# PwrAndBias.net
KiCad netlist of a schematic drawn in Altium Designer
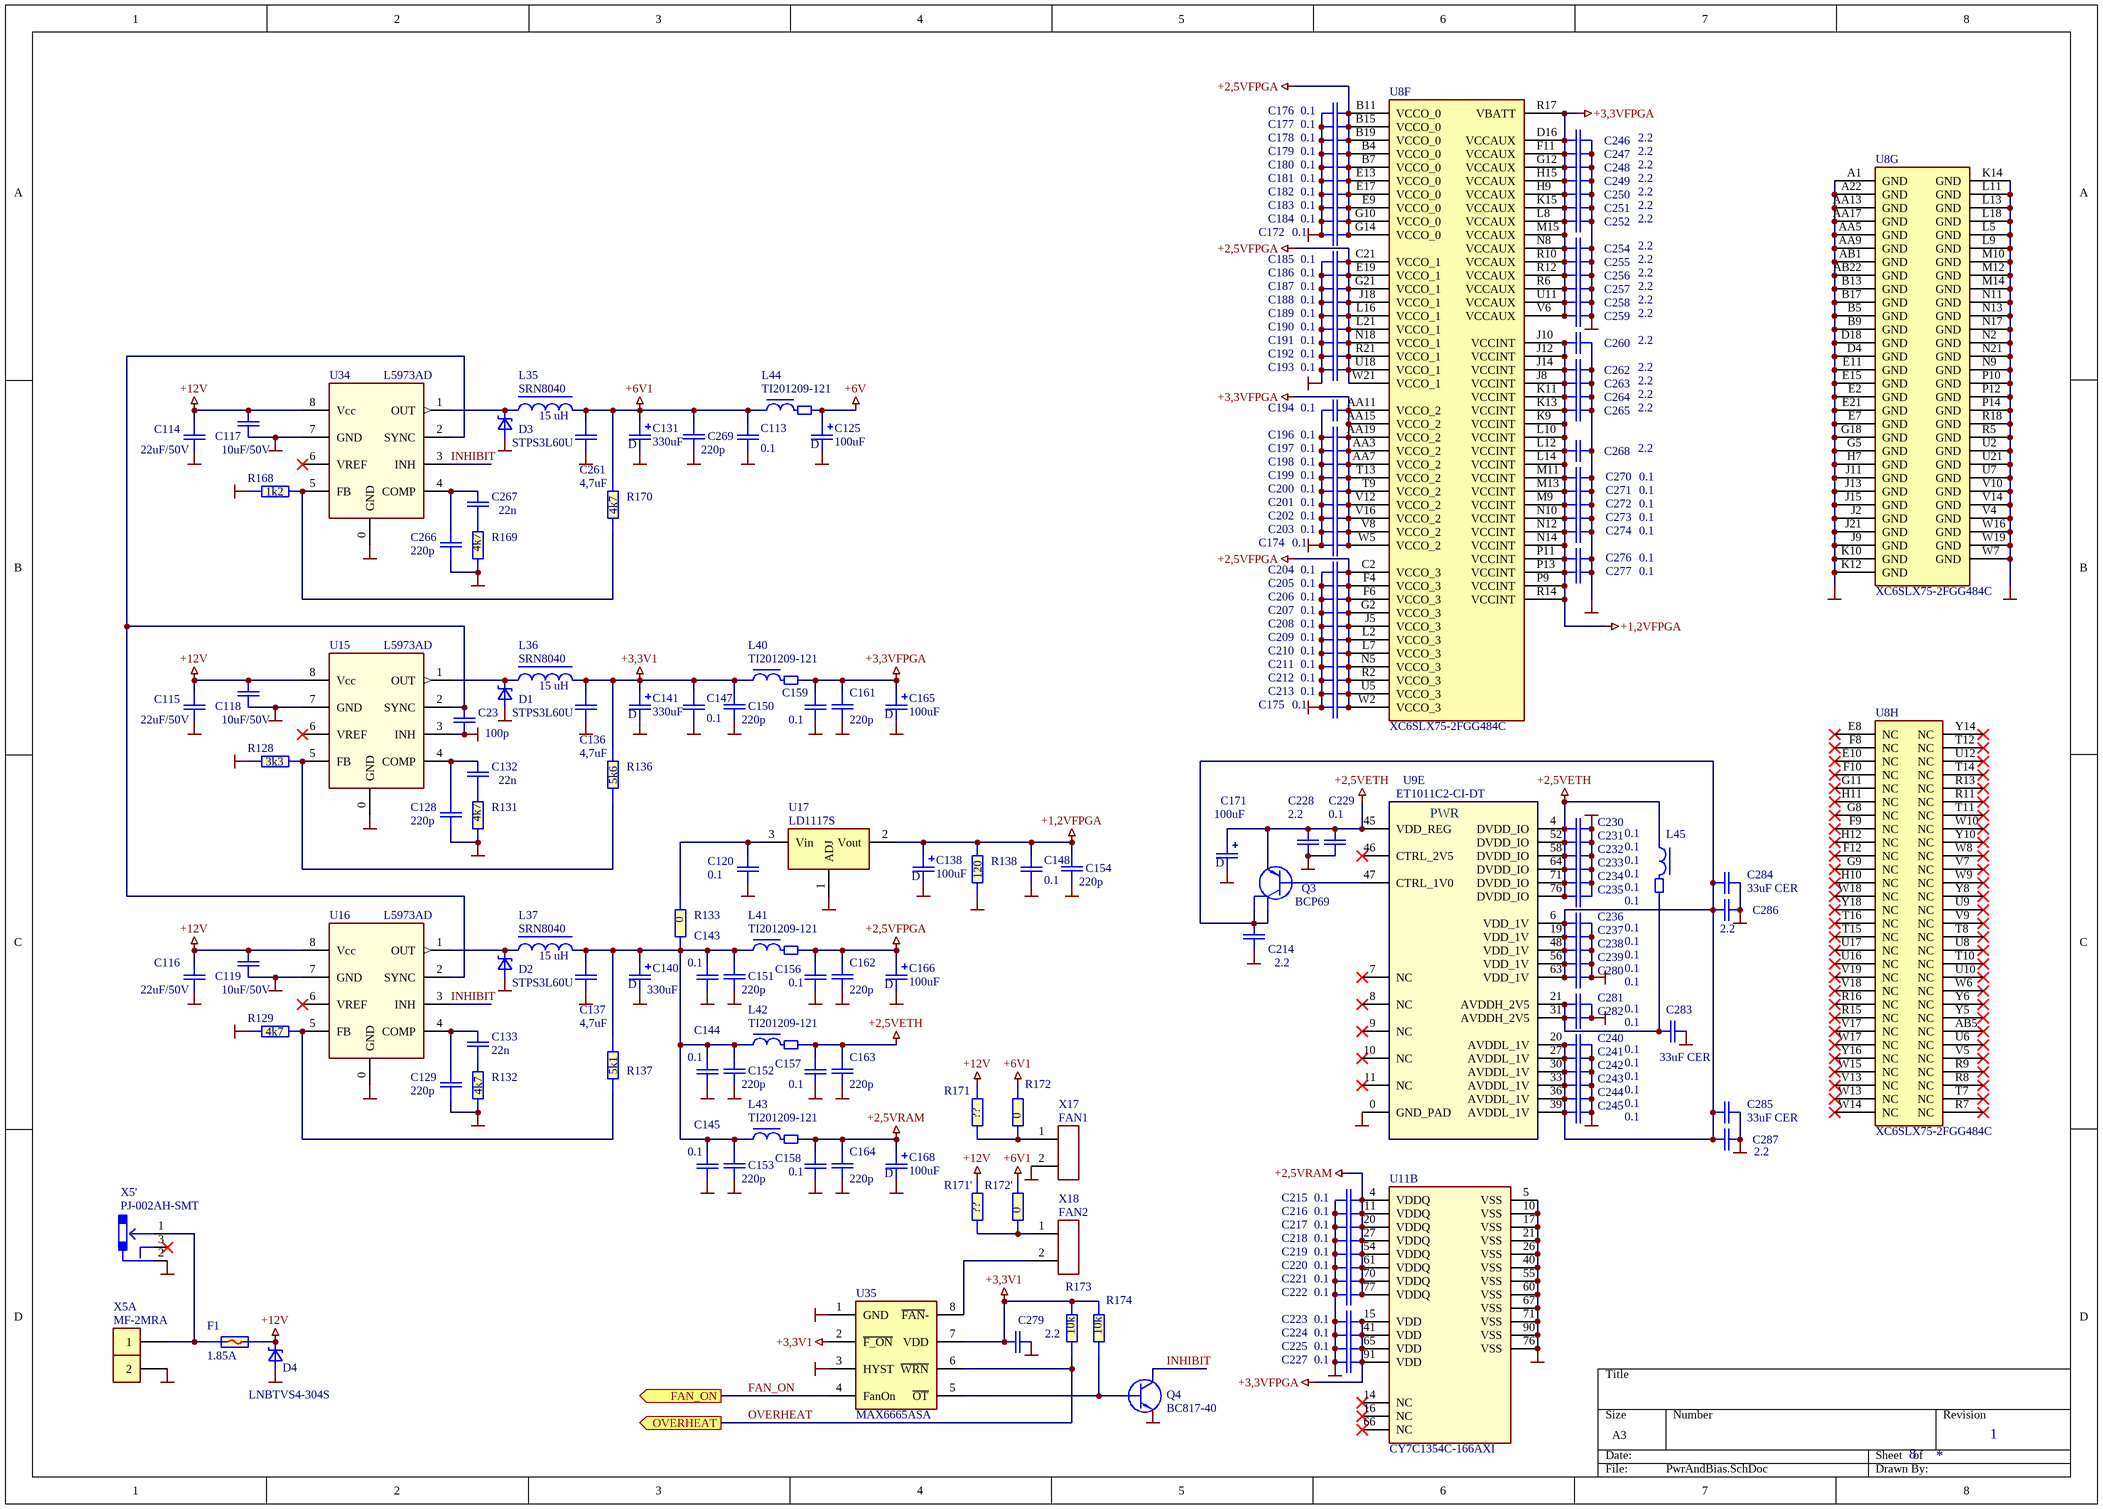
[diagram p0: PwrAndBias.SchDoc]

(export (version "E")
  (design (tool "Eeschema 10.0.6"))
  (components
    (comp (ref "C23")
      (value "100p")
      (footprint "C0603-PHILLIPS")
      (description "Конденсатор")
      (fields (field (name "MANUFACTURER") "MURATA") (field (name "TOLERANCE") "20%"))
      (libsource (lib "altium-import") (part "root_0_mirrored_C0603_"))
    )
    (comp (ref "C113")
      (value "0.1")
      (footprint "C0402-Phillips")
      (description "Конденсатор")
      (fields (field (name "MANUFACTURER") "MURATA") (field (name "TOLERANCE") "20%"))
      (libsource (lib "Capacitors") (part "C0402"))
    )
    (comp (ref "C114")
      (value "22uF/50V")
      (footprint "C2220")
      (description "Конденсатор")
      (fields (field (name "MANUFACTURER") "TDK"))
      (libsource (lib "Capacitors") (part "C2220"))
    )
    (comp (ref "C115")
      (value "22uF/50V")
      (footprint "C2220")
      (description "Конденсатор")
      (fields (field (name "MANUFACTURER") "TDK"))
      (libsource (lib "Capacitors") (part "C2220"))
    )
    (comp (ref "C116")
      (value "22uF/50V")
      (footprint "C2220")
      (description "Конденсатор")
      (fields (field (name "MANUFACTURER") "TDK"))
      (libsource (lib "Capacitors") (part "C2220"))
    )
    (comp (ref "C117")
      (value "10uF/50V")
      (footprint "C1210_H2,5")
      (description "Конденсатор")
      (fields (field (name "MANUFACTURER") "TAIYO YUDEN") (field (name "TOLERANCE") "20%"))
      (libsource (lib "Andy") (part "C1210_H2,5"))
    )
    (comp (ref "C118")
      (value "10uF/50V")
      (footprint "C1210_H2,5")
      (description "Конденсатор")
      (fields (field (name "MANUFACTURER") "TAIYO YUDEN") (field (name "TOLERANCE") "20%"))
      (libsource (lib "Andy") (part "C1210_H2,5"))
    )
    (comp (ref "C119")
      (value "10uF/50V")
      (footprint "C1210_H2,5")
      (description "Конденсатор")
      (fields (field (name "MANUFACTURER") "TAIYO YUDEN") (field (name "TOLERANCE") "20%"))
      (libsource (lib "Andy") (part "C1210_H2,5"))
    )
    (comp (ref "C120")
      (value "0.1")
      (footprint "C0402-Phillips")
      (description "Конденсатор")
      (fields (field (name "MANUFACTURER") "MURATA") (field (name "TOLERANCE") "20%"))
      (libsource (lib "Capacitors") (part "C0402"))
    )
    (comp (ref "C125")
      (value "100uF")
      (footprint "cd7343")
      (description "Конденсатор")
      (fields (field (name "MANUFACTURER") "SPRAGUE"))
      (libsource (lib "altium-import") (part "root_0_CD7343_"))
    )
    (comp (ref "C128")
      (value "220p")
      (footprint "C0603-PHILLIPS")
      (description "Конденсатор")
      (fields (field (name "MANUFACTURER") "MURATA") (field (name "TOLERANCE") "20%"))
      (libsource (lib "altium-import") (part "root_0_C0603_"))
    )
    (comp (ref "C129")
      (value "220p")
      (footprint "C0603-PHILLIPS")
      (description "Конденсатор")
      (fields (field (name "MANUFACTURER") "MURATA") (field (name "TOLERANCE") "20%"))
      (libsource (lib "altium-import") (part "root_0_C0603_"))
    )
    (comp (ref "C131")
      (value "330uF")
      (footprint "cd7343")
      (description "Конденсатор")
      (fields (field (name "MANUFACTURER") "Kemet"))
      (libsource (lib "altium-import") (part "root_0_CD7343_"))
    )
    (comp (ref "C132")
      (value "22n")
      (footprint "C0603-PHILLIPS")
      (description "Конденсатор")
      (fields (field (name "MANUFACTURER") "MURATA") (field (name "TOLERANCE") "20%"))
      (libsource (lib "altium-import") (part "root_0_C0603_"))
    )
    (comp (ref "C133")
      (value "22n")
      (footprint "C0603-PHILLIPS")
      (description "Конденсатор")
      (fields (field (name "MANUFACTURER") "MURATA") (field (name "TOLERANCE") "20%"))
      (libsource (lib "altium-import") (part "root_0_C0603_"))
    )
    (comp (ref "C136")
      (value "4,7uF")
      (footprint "c1206")
      (description "Конденсатор")
      (fields (field (name "MANUFACTURER") "Taiyo Yuden") (field (name "TOLERANCE") "10%"))
      (libsource (lib "altium-import") (part "root_0_C1206_"))
    )
    (comp (ref "C137")
      (value "4,7uF")
      (footprint "c1206")
      (description "Конденсатор")
      (fields (field (name "MANUFACTURER") "Taiyo Yuden") (field (name "TOLERANCE") "10%"))
      (libsource (lib "altium-import") (part "root_0_C1206_"))
    )
    (comp (ref "C138")
      (value "100uF")
      (footprint "cd7343")
      (description "Конденсатор")
      (fields (field (name "MANUFACTURER") "SPRAGUE"))
      (libsource (lib "altium-import") (part "root_0_CD7343_"))
    )
    (comp (ref "C140")
      (value "330uF")
      (footprint "cd7343")
      (description "Конденсатор")
      (fields (field (name "MANUFACTURER") "Kemet"))
      (libsource (lib "altium-import") (part "root_0_CD7343_"))
    )
    (comp (ref "C141")
      (value "330uF")
      (footprint "cd7343")
      (description "Конденсатор")
      (fields (field (name "MANUFACTURER") "Kemet"))
      (libsource (lib "altium-import") (part "root_0_CD7343_"))
    )
    (comp (ref "C143")
      (value "0.1")
      (footprint "C0402-Phillips")
      (description "Конденсатор")
      (fields (field (name "MANUFACTURER") "MURATA") (field (name "TOLERANCE") "20%"))
      (libsource (lib "Capacitors") (part "C0402"))
    )
    (comp (ref "C144")
      (value "0.1")
      (footprint "C0402-Phillips")
      (description "Конденсатор")
      (fields (field (name "MANUFACTURER") "MURATA") (field (name "TOLERANCE") "20%"))
      (libsource (lib "Capacitors") (part "C0402"))
    )
    (comp (ref "C145")
      (value "0.1")
      (footprint "C0402-Phillips")
      (description "Конденсатор")
      (fields (field (name "MANUFACTURER") "MURATA") (field (name "TOLERANCE") "20%"))
      (libsource (lib "Capacitors") (part "C0402"))
    )
    (comp (ref "C147")
      (value "0.1")
      (footprint "C0402-Phillips")
      (description "Конденсатор")
      (fields (field (name "MANUFACTURER") "MURATA") (field (name "TOLERANCE") "20%"))
      (libsource (lib "Capacitors") (part "C0402"))
    )
    (comp (ref "C148")
      (value "0.1")
      (footprint "C0402-Phillips")
      (description "Конденсатор")
      (fields (field (name "MANUFACTURER") "MURATA") (field (name "TOLERANCE") "20%"))
      (libsource (lib "Capacitors") (part "C0402"))
    )
    (comp (ref "C150")
      (value "220p")
      (footprint "C0603-PHILLIPS")
      (description "Конденсатор")
      (fields (field (name "MANUFACTURER") "MURATA") (field (name "TOLERANCE") "20%"))
      (libsource (lib "altium-import") (part "root_0_C0603_"))
    )
    (comp (ref "C151")
      (value "220p")
      (footprint "C0603-PHILLIPS")
      (description "Конденсатор")
      (fields (field (name "MANUFACTURER") "MURATA") (field (name "TOLERANCE") "20%"))
      (libsource (lib "altium-import") (part "root_0_C0603_"))
    )
    (comp (ref "C152")
      (value "220p")
      (footprint "C0603-PHILLIPS")
      (description "Конденсатор")
      (fields (field (name "MANUFACTURER") "MURATA") (field (name "TOLERANCE") "20%"))
      (libsource (lib "altium-import") (part "root_0_C0603_"))
    )
    (comp (ref "C153")
      (value "220p")
      (footprint "C0603-PHILLIPS")
      (description "Конденсатор")
      (fields (field (name "MANUFACTURER") "MURATA") (field (name "TOLERANCE") "20%"))
      (libsource (lib "altium-import") (part "root_0_C0603_"))
    )
    (comp (ref "C154")
      (value "220p")
      (footprint "C0603-PHILLIPS")
      (description "Конденсатор")
      (fields (field (name "MANUFACTURER") "MURATA") (field (name "TOLERANCE") "20%"))
      (libsource (lib "altium-import") (part "root_0_C0603_"))
    )
    (comp (ref "C156")
      (value "0.1")
      (footprint "C0402-Phillips")
      (description "Конденсатор")
      (fields (field (name "MANUFACTURER") "MURATA") (field (name "TOLERANCE") "20%"))
      (libsource (lib "Capacitors") (part "C0402"))
    )
    (comp (ref "C157")
      (value "0.1")
      (footprint "C0402-Phillips")
      (description "Конденсатор")
      (fields (field (name "MANUFACTURER") "MURATA") (field (name "TOLERANCE") "20%"))
      (libsource (lib "Capacitors") (part "C0402"))
    )
    (comp (ref "C158")
      (value "0.1")
      (footprint "C0402-Phillips")
      (description "Конденсатор")
      (fields (field (name "MANUFACTURER") "MURATA") (field (name "TOLERANCE") "20%"))
      (libsource (lib "Capacitors") (part "C0402"))
    )
    (comp (ref "C159")
      (value "0.1")
      (footprint "C0402-Phillips")
      (description "Конденсатор")
      (fields (field (name "MANUFACTURER") "MURATA") (field (name "TOLERANCE") "20%"))
      (libsource (lib "Capacitors") (part "C0402"))
    )
    (comp (ref "C161")
      (value "220p")
      (footprint "C0603-PHILLIPS")
      (description "Конденсатор")
      (fields (field (name "MANUFACTURER") "MURATA") (field (name "TOLERANCE") "20%"))
      (libsource (lib "altium-import") (part "root_0_C0603_"))
    )
    (comp (ref "C162")
      (value "220p")
      (footprint "C0603-PHILLIPS")
      (description "Конденсатор")
      (fields (field (name "MANUFACTURER") "MURATA") (field (name "TOLERANCE") "20%"))
      (libsource (lib "altium-import") (part "root_0_C0603_"))
    )
    (comp (ref "C163")
      (value "220p")
      (footprint "C0603-PHILLIPS")
      (description "Конденсатор")
      (fields (field (name "MANUFACTURER") "MURATA") (field (name "TOLERANCE") "20%"))
      (libsource (lib "altium-import") (part "root_0_C0603_"))
    )
    (comp (ref "C164")
      (value "220p")
      (footprint "C0603-PHILLIPS")
      (description "Конденсатор")
      (fields (field (name "MANUFACTURER") "MURATA") (field (name "TOLERANCE") "20%"))
      (libsource (lib "altium-import") (part "root_0_C0603_"))
    )
    (comp (ref "C165")
      (value "100uF")
      (footprint "cd7343")
      (description "Конденсатор")
      (fields (field (name "MANUFACTURER") "SPRAGUE"))
      (libsource (lib "altium-import") (part "root_0_CD7343_"))
    )
    (comp (ref "C166")
      (value "100uF")
      (footprint "cd7343")
      (description "Конденсатор")
      (fields (field (name "MANUFACTURER") "SPRAGUE"))
      (libsource (lib "altium-import") (part "root_0_CD7343_"))
    )
    (comp (ref "C168")
      (value "100uF")
      (footprint "cd7343")
      (description "Конденсатор")
      (fields (field (name "MANUFACTURER") "SPRAGUE"))
      (libsource (lib "altium-import") (part "root_0_CD7343_"))
    )
    (comp (ref "C171")
      (value "100uF")
      (footprint "cd7343")
      (description "Конденсатор")
      (fields (field (name "MANUFACTURER") "SPRAGUE"))
      (libsource (lib "altium-import") (part "root_0_CD7343_"))
    )
    (comp (ref "C172")
      (value "0.1")
      (footprint "C0402-cirq")
      (description "Конденсатор")
      (fields (field (name "MANUFACTURER") "MURATA") (field (name "TOLERANCE") "20%"))
      (libsource (lib "Capacitors") (part "C0402"))
    )
    (comp (ref "C174")
      (value "0.1")
      (footprint "C0402-cirq")
      (description "Конденсатор")
      (fields (field (name "MANUFACTURER") "MURATA") (field (name "TOLERANCE") "20%"))
      (libsource (lib "Capacitors") (part "C0402"))
    )
    (comp (ref "C175")
      (value "0.1")
      (footprint "C0402-cirq")
      (description "Конденсатор")
      (fields (field (name "MANUFACTURER") "MURATA") (field (name "TOLERANCE") "20%"))
      (libsource (lib "Capacitors") (part "C0402"))
    )
    (comp (ref "C176")
      (value "0.1")
      (footprint "C0402-cirq")
      (description "Конденсатор")
      (fields (field (name "MANUFACTURER") "MURATA") (field (name "TOLERANCE") "20%"))
      (libsource (lib "Capacitors") (part "C0402"))
    )
    (comp (ref "C177")
      (value "0.1")
      (footprint "C0402-cirq")
      (description "Конденсатор")
      (fields (field (name "MANUFACTURER") "MURATA") (field (name "TOLERANCE") "20%"))
      (libsource (lib "Capacitors") (part "C0402"))
    )
    (comp (ref "C178")
      (value "0.1")
      (footprint "C0402-cirq")
      (description "Конденсатор")
      (fields (field (name "MANUFACTURER") "MURATA") (field (name "TOLERANCE") "20%"))
      (libsource (lib "Capacitors") (part "C0402"))
    )
    (comp (ref "C179")
      (value "0.1")
      (footprint "C0402-cirq")
      (description "Конденсатор")
      (fields (field (name "MANUFACTURER") "MURATA") (field (name "TOLERANCE") "20%"))
      (libsource (lib "Capacitors") (part "C0402"))
    )
    (comp (ref "C180")
      (value "0.1")
      (footprint "C0402-cirq")
      (description "Конденсатор")
      (fields (field (name "MANUFACTURER") "MURATA") (field (name "TOLERANCE") "20%"))
      (libsource (lib "Capacitors") (part "C0402"))
    )
    (comp (ref "C181")
      (value "0.1")
      (footprint "C0402-cirq")
      (description "Конденсатор")
      (fields (field (name "MANUFACTURER") "MURATA") (field (name "TOLERANCE") "20%"))
      (libsource (lib "Capacitors") (part "C0402"))
    )
    (comp (ref "C182")
      (value "0.1")
      (footprint "C0402-cirq")
      (description "Конденсатор")
      (fields (field (name "MANUFACTURER") "MURATA") (field (name "TOLERANCE") "20%"))
      (libsource (lib "Capacitors") (part "C0402"))
    )
    (comp (ref "C183")
      (value "0.1")
      (footprint "C0402-cirq")
      (description "Конденсатор")
      (fields (field (name "MANUFACTURER") "MURATA") (field (name "TOLERANCE") "20%"))
      (libsource (lib "Capacitors") (part "C0402"))
    )
    (comp (ref "C184")
      (value "0.1")
      (footprint "C0402-cirq")
      (description "Конденсатор")
      (fields (field (name "MANUFACTURER") "MURATA") (field (name "TOLERANCE") "20%"))
      (libsource (lib "Capacitors") (part "C0402"))
    )
    (comp (ref "C185")
      (value "0.1")
      (footprint "C0402-cirq")
      (description "Конденсатор")
      (fields (field (name "MANUFACTURER") "MURATA") (field (name "TOLERANCE") "20%"))
      (libsource (lib "Capacitors") (part "C0402"))
    )
    (comp (ref "C186")
      (value "0.1")
      (footprint "C0402-cirq")
      (description "Конденсатор")
      (fields (field (name "MANUFACTURER") "MURATA") (field (name "TOLERANCE") "20%"))
      (libsource (lib "Capacitors") (part "C0402"))
    )
    (comp (ref "C187")
      (value "0.1")
      (footprint "C0402-cirq")
      (description "Конденсатор")
      (fields (field (name "MANUFACTURER") "MURATA") (field (name "TOLERANCE") "20%"))
      (libsource (lib "Capacitors") (part "C0402"))
    )
    (comp (ref "C188")
      (value "0.1")
      (footprint "C0402-cirq")
      (description "Конденсатор")
      (fields (field (name "MANUFACTURER") "MURATA") (field (name "TOLERANCE") "20%"))
      (libsource (lib "Capacitors") (part "C0402"))
    )
    (comp (ref "C189")
      (value "0.1")
      (footprint "C0402-cirq")
      (description "Конденсатор")
      (fields (field (name "MANUFACTURER") "MURATA") (field (name "TOLERANCE") "20%"))
      (libsource (lib "Capacitors") (part "C0402"))
    )
    (comp (ref "C190")
      (value "0.1")
      (footprint "C0402-cirq")
      (description "Конденсатор")
      (fields (field (name "MANUFACTURER") "MURATA") (field (name "TOLERANCE") "20%"))
      (libsource (lib "Capacitors") (part "C0402"))
    )
    (comp (ref "C191")
      (value "0.1")
      (footprint "C0402-cirq")
      (description "Конденсатор")
      (fields (field (name "MANUFACTURER") "MURATA") (field (name "TOLERANCE") "20%"))
      (libsource (lib "Capacitors") (part "C0402"))
    )
    (comp (ref "C192")
      (value "0.1")
      (footprint "C0402-cirq")
      (description "Конденсатор")
      (fields (field (name "MANUFACTURER") "MURATA") (field (name "TOLERANCE") "20%"))
      (libsource (lib "Capacitors") (part "C0402"))
    )
    (comp (ref "C193")
      (value "0.1")
      (footprint "C0402-cirq")
      (description "Конденсатор")
      (fields (field (name "MANUFACTURER") "MURATA") (field (name "TOLERANCE") "20%"))
      (libsource (lib "Capacitors") (part "C0402"))
    )
    (comp (ref "C194")
      (value "0.1")
      (footprint "C0402-cirq")
      (description "Конденсатор")
      (fields (field (name "MANUFACTURER") "MURATA") (field (name "TOLERANCE") "20%"))
      (libsource (lib "Capacitors") (part "C0402"))
    )
    (comp (ref "C196")
      (value "0.1")
      (footprint "C0402-cirq")
      (description "Конденсатор")
      (fields (field (name "MANUFACTURER") "MURATA") (field (name "TOLERANCE") "20%"))
      (libsource (lib "Capacitors") (part "C0402"))
    )
    (comp (ref "C197")
      (value "0.1")
      (footprint "C0402-cirq")
      (description "Конденсатор")
      (fields (field (name "MANUFACTURER") "MURATA") (field (name "TOLERANCE") "20%"))
      (libsource (lib "Capacitors") (part "C0402"))
    )
    (comp (ref "C198")
      (value "0.1")
      (footprint "C0402-cirq")
      (description "Конденсатор")
      (fields (field (name "MANUFACTURER") "MURATA") (field (name "TOLERANCE") "20%"))
      (libsource (lib "Capacitors") (part "C0402"))
    )
    (comp (ref "C199")
      (value "0.1")
      (footprint "C0402-cirq")
      (description "Конденсатор")
      (fields (field (name "MANUFACTURER") "MURATA") (field (name "TOLERANCE") "20%"))
      (libsource (lib "Capacitors") (part "C0402"))
    )
    (comp (ref "C200")
      (value "0.1")
      (footprint "C0402-cirq")
      (description "Конденсатор")
      (fields (field (name "MANUFACTURER") "MURATA") (field (name "TOLERANCE") "20%"))
      (libsource (lib "Capacitors") (part "C0402"))
    )
    (comp (ref "C201")
      (value "0.1")
      (footprint "C0402-cirq")
      (description "Конденсатор")
      (fields (field (name "MANUFACTURER") "MURATA") (field (name "TOLERANCE") "20%"))
      (libsource (lib "Capacitors") (part "C0402"))
    )
    (comp (ref "C202")
      (value "0.1")
      (footprint "C0402-cirq")
      (description "Конденсатор")
      (fields (field (name "MANUFACTURER") "MURATA") (field (name "TOLERANCE") "20%"))
      (libsource (lib "Capacitors") (part "C0402"))
    )
    (comp (ref "C203")
      (value "0.1")
      (footprint "C0402-cirq")
      (description "Конденсатор")
      (fields (field (name "MANUFACTURER") "MURATA") (field (name "TOLERANCE") "20%"))
      (libsource (lib "Capacitors") (part "C0402"))
    )
    (comp (ref "C204")
      (value "0.1")
      (footprint "C0402-cirq")
      (description "Конденсатор")
      (fields (field (name "MANUFACTURER") "MURATA") (field (name "TOLERANCE") "20%"))
      (libsource (lib "Capacitors") (part "C0402"))
    )
    (comp (ref "C205")
      (value "0.1")
      (footprint "C0402-cirq")
      (description "Конденсатор")
      (fields (field (name "MANUFACTURER") "MURATA") (field (name "TOLERANCE") "20%"))
      (libsource (lib "Capacitors") (part "C0402"))
    )
    (comp (ref "C206")
      (value "0.1")
      (footprint "C0402-cirq")
      (description "Конденсатор")
      (fields (field (name "MANUFACTURER") "MURATA") (field (name "TOLERANCE") "20%"))
      (libsource (lib "Capacitors") (part "C0402"))
    )
    (comp (ref "C207")
      (value "0.1")
      (footprint "C0402-cirq")
      (description "Конденсатор")
      (fields (field (name "MANUFACTURER") "MURATA") (field (name "TOLERANCE") "20%"))
      (libsource (lib "Capacitors") (part "C0402"))
    )
    (comp (ref "C208")
      (value "0.1")
      (footprint "C0402-cirq")
      (description "Конденсатор")
      (fields (field (name "MANUFACTURER") "MURATA") (field (name "TOLERANCE") "20%"))
      (libsource (lib "Capacitors") (part "C0402"))
    )
    (comp (ref "C209")
      (value "0.1")
      (footprint "C0402-cirq")
      (description "Конденсатор")
      (fields (field (name "MANUFACTURER") "MURATA") (field (name "TOLERANCE") "20%"))
      (libsource (lib "Capacitors") (part "C0402"))
    )
    (comp (ref "C210")
      (value "0.1")
      (footprint "C0402-cirq")
      (description "Конденсатор")
      (fields (field (name "MANUFACTURER") "MURATA") (field (name "TOLERANCE") "20%"))
      (libsource (lib "Capacitors") (part "C0402"))
    )
    (comp (ref "C211")
      (value "0.1")
      (footprint "C0402-cirq")
      (description "Конденсатор")
      (fields (field (name "MANUFACTURER") "MURATA") (field (name "TOLERANCE") "20%"))
      (libsource (lib "Capacitors") (part "C0402"))
    )
    (comp (ref "C212")
      (value "0.1")
      (footprint "C0402-cirq")
      (description "Конденсатор")
      (fields (field (name "MANUFACTURER") "MURATA") (field (name "TOLERANCE") "20%"))
      (libsource (lib "Capacitors") (part "C0402"))
    )
    (comp (ref "C213")
      (value "0.1")
      (footprint "C0402-cirq")
      (description "Конденсатор")
      (fields (field (name "MANUFACTURER") "MURATA") (field (name "TOLERANCE") "20%"))
      (libsource (lib "Capacitors") (part "C0402"))
    )
    (comp (ref "C214")
      (value "2.2")
      (footprint "C0402-Phillips")
      (description "Конденсатор")
      (fields (field (name "MANUFACTURER") "MURATA") (field (name "TOLERANCE") "20%"))
      (libsource (lib "Capacitors") (part "C0402"))
    )
    (comp (ref "C215")
      (value "0.1")
      (footprint "C0402-Phillips")
      (description "Конденсатор")
      (fields (field (name "MANUFACTURER") "MURATA") (field (name "TOLERANCE") "20%"))
      (libsource (lib "Capacitors") (part "C0402"))
    )
    (comp (ref "C216")
      (value "0.1")
      (footprint "C0402-Phillips")
      (description "Конденсатор")
      (fields (field (name "MANUFACTURER") "MURATA") (field (name "TOLERANCE") "20%"))
      (libsource (lib "Capacitors") (part "C0402"))
    )
    (comp (ref "C217")
      (value "0.1")
      (footprint "C0402-Phillips")
      (description "Конденсатор")
      (fields (field (name "MANUFACTURER") "MURATA") (field (name "TOLERANCE") "20%"))
      (libsource (lib "Capacitors") (part "C0402"))
    )
    (comp (ref "C218")
      (value "0.1")
      (footprint "C0402-Phillips")
      (description "Конденсатор")
      (fields (field (name "MANUFACTURER") "MURATA") (field (name "TOLERANCE") "20%"))
      (libsource (lib "Capacitors") (part "C0402"))
    )
    (comp (ref "C219")
      (value "0.1")
      (footprint "C0402-Phillips")
      (description "Конденсатор")
      (fields (field (name "MANUFACTURER") "MURATA") (field (name "TOLERANCE") "20%"))
      (libsource (lib "Capacitors") (part "C0402"))
    )
    (comp (ref "C220")
      (value "0.1")
      (footprint "C0402-Phillips")
      (description "Конденсатор")
      (fields (field (name "MANUFACTURER") "MURATA") (field (name "TOLERANCE") "20%"))
      (libsource (lib "Capacitors") (part "C0402"))
    )
    (comp (ref "C221")
      (value "0.1")
      (footprint "C0402-Phillips")
      (description "Конденсатор")
      (fields (field (name "MANUFACTURER") "MURATA") (field (name "TOLERANCE") "20%"))
      (libsource (lib "Capacitors") (part "C0402"))
    )
    (comp (ref "C222")
      (value "0.1")
      (footprint "C0402-Phillips")
      (description "Конденсатор")
      (fields (field (name "MANUFACTURER") "MURATA") (field (name "TOLERANCE") "20%"))
      (libsource (lib "Capacitors") (part "C0402"))
    )
    (comp (ref "C223")
      (value "0.1")
      (footprint "C0402-Phillips")
      (description "Конденсатор")
      (fields (field (name "MANUFACTURER") "MURATA") (field (name "TOLERANCE") "20%"))
      (libsource (lib "Capacitors") (part "C0402"))
    )
    (comp (ref "C224")
      (value "0.1")
      (footprint "C0402-Phillips")
      (description "Конденсатор")
      (fields (field (name "MANUFACTURER") "MURATA") (field (name "TOLERANCE") "20%"))
      (libsource (lib "Capacitors") (part "C0402"))
    )
    (comp (ref "C225")
      (value "0.1")
      (footprint "C0402-Phillips")
      (description "Конденсатор")
      (fields (field (name "MANUFACTURER") "MURATA") (field (name "TOLERANCE") "20%"))
      (libsource (lib "Capacitors") (part "C0402"))
    )
    (comp (ref "C227")
      (value "0.1")
      (footprint "C0402-Phillips")
      (description "Конденсатор")
      (fields (field (name "MANUFACTURER") "MURATA") (field (name "TOLERANCE") "20%"))
      (libsource (lib "Capacitors") (part "C0402"))
    )
    (comp (ref "C228")
      (value "2.2")
      (footprint "C0402-Phillips")
      (description "Конденсатор")
      (fields (field (name "MANUFACTURER") "MURATA") (field (name "TOLERANCE") "20%"))
      (libsource (lib "Capacitors") (part "C0402"))
    )
    (comp (ref "C229")
      (value "0.1")
      (footprint "C0402-Phillips")
      (description "Конденсатор")
      (fields (field (name "MANUFACTURER") "MURATA") (field (name "TOLERANCE") "20%"))
      (libsource (lib "Capacitors") (part "C0402"))
    )
    (comp (ref "C230")
      (value "0.1")
      (footprint "C0402-Phillips")
      (description "Конденсатор")
      (fields (field (name "MANUFACTURER") "MURATA") (field (name "TOLERANCE") "20%"))
      (libsource (lib "Capacitors") (part "C0402"))
    )
    (comp (ref "C231")
      (value "0.1")
      (footprint "C0402-Phillips")
      (description "Конденсатор")
      (fields (field (name "MANUFACTURER") "MURATA") (field (name "TOLERANCE") "20%"))
      (libsource (lib "Capacitors") (part "C0402"))
    )
    (comp (ref "C232")
      (value "0.1")
      (footprint "C0402-Phillips")
      (description "Конденсатор")
      (fields (field (name "MANUFACTURER") "MURATA") (field (name "TOLERANCE") "20%"))
      (libsource (lib "Capacitors") (part "C0402"))
    )
    (comp (ref "C233")
      (value "0.1")
      (footprint "C0402-Phillips")
      (description "Конденсатор")
      (fields (field (name "MANUFACTURER") "MURATA") (field (name "TOLERANCE") "20%"))
      (libsource (lib "Capacitors") (part "C0402"))
    )
    (comp (ref "C234")
      (value "0.1")
      (footprint "C0402-Phillips")
      (description "Конденсатор")
      (fields (field (name "MANUFACTURER") "MURATA") (field (name "TOLERANCE") "20%"))
      (libsource (lib "Capacitors") (part "C0402"))
    )
    (comp (ref "C235")
      (value "0.1")
      (footprint "C0402-Phillips")
      (description "Конденсатор")
      (fields (field (name "MANUFACTURER") "MURATA") (field (name "TOLERANCE") "20%"))
      (libsource (lib "Capacitors") (part "C0402"))
    )
    (comp (ref "C236")
      (value "0.1")
      (footprint "C0402-Phillips")
      (description "Конденсатор")
      (fields (field (name "MANUFACTURER") "MURATA") (field (name "TOLERANCE") "20%"))
      (libsource (lib "Capacitors") (part "C0402"))
    )
    (comp (ref "C237")
      (value "0.1")
      (footprint "C0402-Phillips")
      (description "Конденсатор")
      (fields (field (name "MANUFACTURER") "MURATA") (field (name "TOLERANCE") "20%"))
      (libsource (lib "Capacitors") (part "C0402"))
    )
    (comp (ref "C238")
      (value "0.1")
      (footprint "C0402-Phillips")
      (description "Конденсатор")
      (fields (field (name "MANUFACTURER") "MURATA") (field (name "TOLERANCE") "20%"))
      (libsource (lib "Capacitors") (part "C0402"))
    )
    (comp (ref "C239")
      (value "0.1")
      (footprint "C0402-Phillips")
      (description "Конденсатор")
      (fields (field (name "MANUFACTURER") "MURATA") (field (name "TOLERANCE") "20%"))
      (libsource (lib "Capacitors") (part "C0402"))
    )
    (comp (ref "C240")
      (value "0.1")
      (footprint "C0402-Phillips")
      (description "Конденсатор")
      (fields (field (name "MANUFACTURER") "MURATA") (field (name "TOLERANCE") "20%"))
      (libsource (lib "Capacitors") (part "C0402"))
    )
    (comp (ref "C241")
      (value "0.1")
      (footprint "C0402-Phillips")
      (description "Конденсатор")
      (fields (field (name "MANUFACTURER") "MURATA") (field (name "TOLERANCE") "20%"))
      (libsource (lib "Capacitors") (part "C0402"))
    )
    (comp (ref "C242")
      (value "0.1")
      (footprint "C0402-Phillips")
      (description "Конденсатор")
      (fields (field (name "MANUFACTURER") "MURATA") (field (name "TOLERANCE") "20%"))
      (libsource (lib "Capacitors") (part "C0402"))
    )
    (comp (ref "C243")
      (value "0.1")
      (footprint "C0402-Phillips")
      (description "Конденсатор")
      (fields (field (name "MANUFACTURER") "MURATA") (field (name "TOLERANCE") "20%"))
      (libsource (lib "Capacitors") (part "C0402"))
    )
    (comp (ref "C244")
      (value "0.1")
      (footprint "C0402-Phillips")
      (description "Конденсатор")
      (fields (field (name "MANUFACTURER") "MURATA") (field (name "TOLERANCE") "20%"))
      (libsource (lib "Capacitors") (part "C0402"))
    )
    (comp (ref "C245")
      (value "0.1")
      (footprint "C0402-Phillips")
      (description "Конденсатор")
      (fields (field (name "MANUFACTURER") "MURATA") (field (name "TOLERANCE") "20%"))
      (libsource (lib "Capacitors") (part "C0402"))
    )
    (comp (ref "C246")
      (value "2.2")
      (footprint "C0402-cirq")
      (description "Конденсатор")
      (fields (field (name "MANUFACTURER") "MURATA") (field (name "TOLERANCE") "20%"))
      (libsource (lib "Capacitors") (part "C0402"))
    )
    (comp (ref "C247")
      (value "2.2")
      (footprint "C0402-cirq")
      (description "Конденсатор")
      (fields (field (name "MANUFACTURER") "MURATA") (field (name "TOLERANCE") "20%"))
      (libsource (lib "Capacitors") (part "C0402"))
    )
    (comp (ref "C248")
      (value "2.2")
      (footprint "C0402-cirq")
      (description "Конденсатор")
      (fields (field (name "MANUFACTURER") "MURATA") (field (name "TOLERANCE") "20%"))
      (libsource (lib "Capacitors") (part "C0402"))
    )
    (comp (ref "C249")
      (value "2.2")
      (footprint "C0402-cirq")
      (description "Конденсатор")
      (fields (field (name "MANUFACTURER") "MURATA") (field (name "TOLERANCE") "20%"))
      (libsource (lib "Capacitors") (part "C0402"))
    )
    (comp (ref "C250")
      (value "2.2")
      (footprint "C0402-cirq")
      (description "Конденсатор")
      (fields (field (name "MANUFACTURER") "MURATA") (field (name "TOLERANCE") "20%"))
      (libsource (lib "Capacitors") (part "C0402"))
    )
    (comp (ref "C251")
      (value "2.2")
      (footprint "C0402-cirq")
      (description "Конденсатор")
      (fields (field (name "MANUFACTURER") "MURATA") (field (name "TOLERANCE") "20%"))
      (libsource (lib "Capacitors") (part "C0402"))
    )
    (comp (ref "C252")
      (value "2.2")
      (footprint "C0402-cirq")
      (description "Конденсатор")
      (fields (field (name "MANUFACTURER") "MURATA") (field (name "TOLERANCE") "20%"))
      (libsource (lib "Capacitors") (part "C0402"))
    )
    (comp (ref "C254")
      (value "2.2")
      (footprint "C0402-cirq")
      (description "Конденсатор")
      (fields (field (name "MANUFACTURER") "MURATA") (field (name "TOLERANCE") "20%"))
      (libsource (lib "Capacitors") (part "C0402"))
    )
    (comp (ref "C255")
      (value "2.2")
      (footprint "C0402-cirq")
      (description "Конденсатор")
      (fields (field (name "MANUFACTURER") "MURATA") (field (name "TOLERANCE") "20%"))
      (libsource (lib "Capacitors") (part "C0402"))
    )
    (comp (ref "C256")
      (value "2.2")
      (footprint "C0402-cirq")
      (description "Конденсатор")
      (fields (field (name "MANUFACTURER") "MURATA") (field (name "TOLERANCE") "20%"))
      (libsource (lib "Capacitors") (part "C0402"))
    )
    (comp (ref "C257")
      (value "2.2")
      (footprint "C0402-cirq")
      (description "Конденсатор")
      (fields (field (name "MANUFACTURER") "MURATA") (field (name "TOLERANCE") "20%"))
      (libsource (lib "Capacitors") (part "C0402"))
    )
    (comp (ref "C258")
      (value "2.2")
      (footprint "C0402-cirq")
      (description "Конденсатор")
      (fields (field (name "MANUFACTURER") "MURATA") (field (name "TOLERANCE") "20%"))
      (libsource (lib "Capacitors") (part "C0402"))
    )
    (comp (ref "C259")
      (value "2.2")
      (footprint "C0402-cirq")
      (description "Конденсатор")
      (fields (field (name "MANUFACTURER") "MURATA") (field (name "TOLERANCE") "20%"))
      (libsource (lib "Capacitors") (part "C0402"))
    )
    (comp (ref "C260")
      (value "2.2")
      (footprint "C0402-cirq")
      (description "Конденсатор")
      (fields (field (name "MANUFACTURER") "MURATA") (field (name "TOLERANCE") "20%"))
      (libsource (lib "Capacitors") (part "C0402"))
    )
    (comp (ref "C261")
      (value "4,7uF")
      (footprint "c1206")
      (description "Конденсатор")
      (fields (field (name "MANUFACTURER") "Taiyo Yuden") (field (name "TOLERANCE") "10%"))
      (libsource (lib "altium-import") (part "root_0_C1206_"))
    )
    (comp (ref "C262")
      (value "2.2")
      (footprint "C0402-cirq")
      (description "Конденсатор")
      (fields (field (name "MANUFACTURER") "MURATA") (field (name "TOLERANCE") "20%"))
      (libsource (lib "Capacitors") (part "C0402"))
    )
    (comp (ref "C263")
      (value "2.2")
      (footprint "C0402-cirq")
      (description "Конденсатор")
      (fields (field (name "MANUFACTURER") "MURATA") (field (name "TOLERANCE") "20%"))
      (libsource (lib "Capacitors") (part "C0402"))
    )
    (comp (ref "C264")
      (value "2.2")
      (footprint "C0402-cirq")
      (description "Конденсатор")
      (fields (field (name "MANUFACTURER") "MURATA") (field (name "TOLERANCE") "20%"))
      (libsource (lib "Capacitors") (part "C0402"))
    )
    (comp (ref "C265")
      (value "2.2")
      (footprint "C0402-cirq")
      (description "Конденсатор")
      (fields (field (name "MANUFACTURER") "MURATA") (field (name "TOLERANCE") "20%"))
      (libsource (lib "Capacitors") (part "C0402"))
    )
    (comp (ref "C266")
      (value "220p")
      (footprint "C0603-PHILLIPS")
      (description "Конденсатор")
      (fields (field (name "MANUFACTURER") "MURATA") (field (name "TOLERANCE") "20%"))
      (libsource (lib "altium-import") (part "root_0_C0603_"))
    )
    (comp (ref "C267")
      (value "22n")
      (footprint "C0603-PHILLIPS")
      (description "Конденсатор")
      (fields (field (name "MANUFACTURER") "MURATA") (field (name "TOLERANCE") "20%"))
      (libsource (lib "altium-import") (part "root_0_C0603_"))
    )
    (comp (ref "C268")
      (value "2.2")
      (footprint "C0402-cirq")
      (description "Конденсатор")
      (fields (field (name "MANUFACTURER") "MURATA") (field (name "TOLERANCE") "20%"))
      (libsource (lib "Capacitors") (part "C0402"))
    )
    (comp (ref "C269")
      (value "220p")
      (footprint "C0603-PHILLIPS")
      (description "Конденсатор")
      (fields (field (name "MANUFACTURER") "MURATA") (field (name "TOLERANCE") "20%"))
      (libsource (lib "altium-import") (part "root_0_C0603_"))
    )
    (comp (ref "C270")
      (value "0.1")
      (footprint "C0402-cirq")
      (description "Конденсатор")
      (fields (field (name "MANUFACTURER") "MURATA") (field (name "TOLERANCE") "20%"))
      (libsource (lib "Capacitors") (part "C0402"))
    )
    (comp (ref "C271")
      (value "0.1")
      (footprint "C0402-cirq")
      (description "Конденсатор")
      (fields (field (name "MANUFACTURER") "MURATA") (field (name "TOLERANCE") "20%"))
      (libsource (lib "Capacitors") (part "C0402"))
    )
    (comp (ref "C272")
      (value "0.1")
      (footprint "C0402-cirq")
      (description "Конденсатор")
      (fields (field (name "MANUFACTURER") "MURATA") (field (name "TOLERANCE") "20%"))
      (libsource (lib "Capacitors") (part "C0402"))
    )
    (comp (ref "C273")
      (value "0.1")
      (footprint "C0402-cirq")
      (description "Конденсатор")
      (fields (field (name "MANUFACTURER") "MURATA") (field (name "TOLERANCE") "20%"))
      (libsource (lib "Capacitors") (part "C0402"))
    )
    (comp (ref "C274")
      (value "0.1")
      (footprint "C0402-cirq")
      (description "Конденсатор")
      (fields (field (name "MANUFACTURER") "MURATA") (field (name "TOLERANCE") "20%"))
      (libsource (lib "Capacitors") (part "C0402"))
    )
    (comp (ref "C276")
      (value "0.1")
      (footprint "C0402-cirq")
      (description "Конденсатор")
      (fields (field (name "MANUFACTURER") "MURATA") (field (name "TOLERANCE") "20%"))
      (libsource (lib "Capacitors") (part "C0402"))
    )
    (comp (ref "C277")
      (value "0.1")
      (footprint "C0402-cirq")
      (description "Конденсатор")
      (fields (field (name "MANUFACTURER") "MURATA") (field (name "TOLERANCE") "20%"))
      (libsource (lib "Capacitors") (part "C0402"))
    )
    (comp (ref "C279")
      (value "2.2")
      (footprint "C0402-Phillips")
      (description "Конденсатор")
      (fields (field (name "MANUFACTURER") "MURATA") (field (name "TOLERANCE") "20%"))
      (libsource (lib "Capacitors") (part "C0402"))
    )
    (comp (ref "C280")
      (value "0.1")
      (footprint "C0402-Phillips")
      (description "Конденсатор")
      (fields (field (name "MANUFACTURER") "MURATA") (field (name "TOLERANCE") "20%"))
      (libsource (lib "Capacitors") (part "C0402"))
    )
    (comp (ref "C281")
      (value "0.1")
      (footprint "C0402-Phillips")
      (description "Конденсатор")
      (fields (field (name "MANUFACTURER") "MURATA") (field (name "TOLERANCE") "20%"))
      (libsource (lib "Capacitors") (part "C0402"))
    )
    (comp (ref "C282")
      (value "0.1")
      (footprint "C0402-Phillips")
      (description "Конденсатор")
      (fields (field (name "MANUFACTURER") "MURATA") (field (name "TOLERANCE") "20%"))
      (libsource (lib "Capacitors") (part "C0402"))
    )
    (comp (ref "C283")
      (value "33uF CER")
      (footprint "C0805-Phillips")
      (description "Конденсатор")
      (fields (field (name "MANUFACTURER") "MURATA") (field (name "TOLERANCE") "20%"))
      (libsource (lib "altium-import") (part "root_1_C0805_"))
    )
    (comp (ref "C284")
      (value "33uF CER")
      (footprint "C0805-Phillips")
      (description "Конденсатор")
      (fields (field (name "MANUFACTURER") "MURATA") (field (name "TOLERANCE") "20%"))
      (libsource (lib "altium-import") (part "root_1_C0805_"))
    )
    (comp (ref "C285")
      (value "33uF CER")
      (footprint "C0805-Phillips")
      (description "Конденсатор")
      (fields (field (name "MANUFACTURER") "MURATA") (field (name "TOLERANCE") "20%"))
      (libsource (lib "altium-import") (part "root_1_C0805_"))
    )
    (comp (ref "C286")
      (value "2.2")
      (footprint "C0402-Phillips")
      (description "Конденсатор")
      (fields (field (name "MANUFACTURER") "MURATA") (field (name "TOLERANCE") "20%"))
      (libsource (lib "Capacitors") (part "C0402"))
    )
    (comp (ref "C287")
      (value "2.2")
      (footprint "C0402-Phillips")
      (description "Конденсатор")
      (fields (field (name "MANUFACTURER") "MURATA") (field (name "TOLERANCE") "20%"))
      (libsource (lib "Capacitors") (part "C0402"))
    )
    (comp (ref "D1")
      (value "STPS3L60U")
      (footprint "SMB")
      (description "Диод Шоттки")
      (fields (field (name "MANUFACTURER") "ST"))
      (libsource (lib "Diods") (part "B3x0B"))
    )
    (comp (ref "D2")
      (value "STPS3L60U")
      (footprint "SMB")
      (description "Диод Шоттки")
      (fields (field (name "MANUFACTURER") "ST"))
      (libsource (lib "Diods") (part "B3x0B"))
    )
    (comp (ref "D3")
      (value "STPS3L60U")
      (footprint "SMB")
      (description "Диод Шоттки")
      (fields (field (name "MANUFACTURER") "ST"))
      (libsource (lib "Diods") (part "B3x0B"))
    )
    (comp (ref "D4")
      (value "LNBTVS4-304S")
      (footprint "SMC")
      (description "Диод")
      (fields (field (name "MANUFACTURER") "ST"))
      (libsource (lib "altium-import") (part "root_0_STPS3L40S_"))
    )
    (comp (ref "F1")
      (value "1.85A")
      (footprint "Andy:FUSE2920")
      (description "FUSE PTC resetable")
      (fields (field (name "MANUFACTURER") "Bel Fuse"))
      (libsource (lib "Andy") (part "FUSE_PTC"))
    )
    (comp (ref "L35")
      (value "15 uH")
      (footprint "SRN8040")
      (description "Индуктивность")
      (fields (field (name "MANUFACTURER") "BOURNS") (field (name "NAME") "SRN8040"))
      (libsource (lib "Andy") (part "L-SRN8040"))
    )
    (comp (ref "L36")
      (value "15 uH")
      (footprint "SRN8040")
      (description "Индуктивность")
      (fields (field (name "MANUFACTURER") "BOURNS") (field (name "NAME") "SRN8040"))
      (libsource (lib "Andy") (part "L-SRN8040"))
    )
    (comp (ref "L37")
      (value "15 uH")
      (footprint "SRN8040")
      (description "Индуктивность")
      (fields (field (name "MANUFACTURER") "BOURNS") (field (name "NAME") "SRN8040"))
      (libsource (lib "Andy") (part "L-SRN8040"))
    )
    (comp (ref "L40")
      (value "TI201209-121")
      (footprint "TI2012-Phillips")
      (description "Дроссель ЭМС")
      (fields (field (name "MANUFACTURER") "MURATA"))
      (libsource (lib "Andy") (part "TI2012_1"))
    )
    (comp (ref "L41")
      (value "TI201209-121")
      (footprint "TI2012-Phillips")
      (description "Дроссель ЭМС")
      (fields (field (name "MANUFACTURER") "MURATA"))
      (libsource (lib "Andy") (part "TI2012_1"))
    )
    (comp (ref "L42")
      (value "TI201209-121")
      (footprint "TI2012-Phillips")
      (description "Дроссель ЭМС")
      (fields (field (name "MANUFACTURER") "MURATA"))
      (libsource (lib "Andy") (part "TI2012_1"))
    )
    (comp (ref "L43")
      (value "TI201209-121")
      (footprint "TI2012-Phillips")
      (description "Дроссель ЭМС")
      (fields (field (name "MANUFACTURER") "MURATA"))
      (libsource (lib "Andy") (part "TI2012_1"))
    )
    (comp (ref "L44")
      (value "TI201209-121")
      (footprint "TI2012-Phillips")
      (description "Дроссель ЭМС")
      (fields (field (name "MANUFACTURER") "MURATA"))
      (libsource (lib "Andy") (part "TI2012_1"))
    )
    (comp (ref "L45")
      (value "TI160808U601")
      (footprint "Ti160808-Phillips")
      (description "Дроссель ЭМС")
      (fields (field (name "MANUFACTURER") "MURATA"))
      (libsource (lib "altium-import") (part "root_3_TI160808_"))
    )
    (comp (ref "Q3")
      (value "BCP69")
      (footprint "SOT-223")
      (description "Транзистор")
      (fields (field (name "MANUFACTURER") "INFINEON"))
      (libsource (lib "altium-import") (part "root_0_mirrored_BCP69_"))
    )
    (comp (ref "Q4")
      (value "BC817-40")
      (footprint "SOT23-Philips")
      (description "Транзистор")
      (fields (field (name "MANUFACTURER") "Philips"))
      (libsource (lib "Transistors") (part "BC 817"))
    )
    (comp (ref "R128")
      (value "3k3")
      (footprint "R0603-PHILLIPS")
      (description "Резистор")
      (fields (field (name "MANUFACTURER") "YAGEO") (field (name "TOLERANCE") "5%"))
      (libsource (lib "altium-import") (part "root_1_R0603_"))
    )
    (comp (ref "R129")
      (value "4k7")
      (footprint "R0603-PHILLIPS")
      (description "Резистор")
      (fields (field (name "MANUFACTURER") "YAGEO") (field (name "TOLERANCE") "5%"))
      (libsource (lib "altium-import") (part "root_1_R0603_"))
    )
    (comp (ref "R131")
      (value "4k7")
      (footprint "R0603-PHILLIPS")
      (description "Резистор")
      (fields (field (name "MANUFACTURER") "YAGEO") (field (name "TOLERANCE") "5%"))
      (libsource (lib "altium-import") (part "root_0_R0603_"))
    )
    (comp (ref "R132")
      (value "4k7")
      (footprint "R0603-PHILLIPS")
      (description "Резистор")
      (fields (field (name "MANUFACTURER") "YAGEO") (field (name "TOLERANCE") "5%"))
      (libsource (lib "altium-import") (part "root_0_R0603_"))
    )
    (comp (ref "R133")
      (value "0")
      (footprint "R0603-PHILLIPS")
      (description "Резистор")
      (fields (field (name "MANUFACTURER") "YAGEO") (field (name "TOLERANCE") "5%"))
      (libsource (lib "altium-import") (part "root_2_R0603_"))
    )
    (comp (ref "R136")
      (value "5k6")
      (footprint "R0603-PHILLIPS")
      (description "Резистор")
      (fields (field (name "MANUFACTURER") "YAGEO") (field (name "TOLERANCE") "5%"))
      (libsource (lib "altium-import") (part "root_0_R0603_"))
    )
    (comp (ref "R137")
      (value "5k1")
      (footprint "R0603-PHILLIPS")
      (description "Резистор")
      (fields (field (name "MANUFACTURER") "YAGEO") (field (name "TOLERANCE") "5%"))
      (libsource (lib "altium-import") (part "root_0_R0603_"))
    )
    (comp (ref "R138")
      (value "120")
      (footprint "R0603-PHILLIPS")
      (description "Резистор")
      (fields (field (name "MANUFACTURER") "YAGEO") (field (name "TOLERANCE") "5%"))
      (libsource (lib "altium-import") (part "root_0_R0603_"))
    )
    (comp (ref "R168")
      (value "1k2")
      (footprint "R0603-PHILLIPS")
      (description "Резистор")
      (fields (field (name "MANUFACTURER") "YAGEO") (field (name "TOLERANCE") "5%"))
      (libsource (lib "altium-import") (part "root_1_R0603_"))
    )
    (comp (ref "R169")
      (value "4k7")
      (footprint "R0603-PHILLIPS")
      (description "Резистор")
      (fields (field (name "MANUFACTURER") "YAGEO") (field (name "TOLERANCE") "5%"))
      (libsource (lib "altium-import") (part "root_0_R0603_"))
    )
    (comp (ref "R170")
      (value "4k7")
      (footprint "R0603-PHILLIPS")
      (description "Резистор")
      (fields (field (name "MANUFACTURER") "YAGEO") (field (name "TOLERANCE") "5%"))
      (libsource (lib "altium-import") (part "root_0_R0603_"))
    )
    (comp (ref "R171")
      (value "??")
      (footprint "R0603-PHILLIPS")
      (description "Резистор")
      (fields (field (name "MANUFACTURER") "YAGEO") (field (name "TOLERANCE") "5%"))
      (libsource (lib "altium-import") (part "root_0_R0603_"))
    )
    (comp (ref "R171'")
      (value "??")
      (footprint "R0603-PHILLIPS")
      (description "Резистор")
      (fields (field (name "MANUFACTURER") "YAGEO") (field (name "TOLERANCE") "5%"))
      (libsource (lib "altium-import") (part "root_0_R0603_"))
    )
    (comp (ref "R172")
      (value "0")
      (footprint "R0603-PHILLIPS")
      (description "Резистор")
      (fields (field (name "MANUFACTURER") "YAGEO") (field (name "TOLERANCE") "5%"))
      (libsource (lib "altium-import") (part "root_0_R0603_"))
    )
    (comp (ref "R172'")
      (value "0")
      (footprint "R0603-PHILLIPS")
      (description "Резистор")
      (fields (field (name "MANUFACTURER") "YAGEO") (field (name "TOLERANCE") "5%"))
      (libsource (lib "altium-import") (part "root_0_R0603_"))
    )
    (comp (ref "R173")
      (value "10k")
      (footprint "R0603-PHILLIPS")
      (description "Резистор")
      (fields (field (name "MANUFACTURER") "YAGEO") (field (name "TOLERANCE") "5%"))
      (libsource (lib "altium-import") (part "root_0_R0603_"))
    )
    (comp (ref "R174")
      (value "10k")
      (footprint "R0603-PHILLIPS")
      (description "Резистор")
      (fields (field (name "MANUFACTURER") "YAGEO") (field (name "TOLERANCE") "5%"))
      (libsource (lib "altium-import") (part "root_0_R0603_"))
    )
    (comp (ref "U8")
      (value "XC6SLX75-2FGG484C")
      (footprint "FBGA484")
      (fields (field (name "MANUFACTURER") "Xilinx"))
      (libsource (lib "MicroCircuitsM-Z") (part "XC6SLX75-2FGG484C"))
    )
    (comp (ref "U9")
      (value "ET1011C2-CI-DT")
      (footprint "QFN-84(10x10/0/4mm)with_pad")
      (description "Микросхема")
      (fields (field (name "MANUFACTURER") "LSI"))
      (libsource (lib "altium-import") (part "root_0_ET1011C2-CI-DT_"))
    )
    (comp (ref "U11")
      (value "CY7C1354C-166AXI")
      (footprint "QFP-10020X14/0.65]")
      (description "Микросхема")
      (fields (field (name "MANUFACTURER") "Cypress"))
      (libsource (lib "MicroCircuits0-L") (part "CY7C1354C-166AXI"))
    )
    (comp (ref "U15")
      (value "L5973AD")
      (footprint "SOIC8 - BackGND - 0.4mm dia")
      (description "Микросхема")
      (fields (field (name "MANUFACTURER") "ST"))
      (libsource (lib "altium-import") (part "root_0_mirrored_L5973D_"))
    )
    (comp (ref "U16")
      (value "L5973AD")
      (footprint "SOIC8 - BackGND - 0.4mm dia")
      (description "Микросхема")
      (fields (field (name "MANUFACTURER") "ST"))
      (libsource (lib "altium-import") (part "root_0_mirrored_L5973D_"))
    )
    (comp (ref "U17")
      (value "LD1117S")
      (footprint "Foot3-4pins:SOT-223-1")
      (description "Микросхема")
      (fields (field (name "MANUFACTURER") "STMicro"))
      (libsource (lib "altium-import") (part "root_0_LD1117ADJ_"))
    )
    (comp (ref "U34")
      (value "L5973AD")
      (footprint "SOIC8 - BackGND - 0.4mm dia")
      (description "Микросхема")
      (fields (field (name "MANUFACTURER") "ST"))
      (libsource (lib "altium-import") (part "root_0_mirrored_L5973D_"))
    )
    (comp (ref "U35")
      (value "MAX6665ASA")
      (footprint "SO-8")
      (description "Микросхема")
      (fields (field (name "MANUFACTURER") "Maxim"))
      (libsource (lib "MicroCircuitsM-Z") (part "MAX6665ASA"))
    )
    (comp (ref "X5")
      (value "MF-2MRA")
      (footprint "MF-2MRA")
      (description "Разъем")
      (fields (field (name "MANUFACTURER") "BM"))
      (libsource (lib "altium-import") (part "root_0_mirrored_MF-2MRA_"))
    )
    (comp (ref "X5'")
      (value "PJ-002AH-SMT")
      (footprint "PJ-002AH-SMT")
      (description "Connector")
      (fields (field (name "MANUFACTURER") "CUI"))
      (libsource (lib "Andy") (part "PJ-002AH-SMT"))
    )
    (comp (ref "X17")
      (value "FAN1")
      (footprint "Andy:WF-2")
      (description "Разъем")
      (fields (field (name "MANUFACTURER") "BM"))
      (libsource (lib "Andy") (part "WF-2"))
    )
    (comp (ref "X18")
      (value "FAN2")
      (footprint "Andy:WF-2")
      (description "Разъем")
      (fields (field (name "MANUFACTURER") "BM"))
      (libsource (lib "Andy") (part "WF-2"))
    )
  )
  (nets
    (net (code "1") (name "+1,2VFPGA") (class "Default")
      (node (ref "C138") (pin "1") (pinfunction "+_1") (pintype "passive"))
      (node (ref "C148") (pin "1") (pinfunction "1_1") (pintype "passive"))
      (node (ref "C154") (pin "1") (pinfunction "1_1") (pintype "passive"))
      (node (ref "C260") (pin "1") (pinfunction "1_1") (pintype "passive"))
      (node (ref "C262") (pin "1") (pinfunction "1_1") (pintype "passive"))
      (node (ref "C263") (pin "1") (pinfunction "1_1") (pintype "passive"))
      (node (ref "C264") (pin "1") (pinfunction "1_1") (pintype "passive"))
      (node (ref "C265") (pin "1") (pinfunction "1_1") (pintype "passive"))
      (node (ref "C268") (pin "1") (pinfunction "1_1") (pintype "passive"))
      (node (ref "C270") (pin "1") (pinfunction "1_1") (pintype "passive"))
      (node (ref "C271") (pin "1") (pinfunction "1_1") (pintype "passive"))
      (node (ref "C272") (pin "1") (pinfunction "1_1") (pintype "passive"))
      (node (ref "C273") (pin "1") (pinfunction "1_1") (pintype "passive"))
      (node (ref "C274") (pin "1") (pinfunction "1_1") (pintype "passive"))
      (node (ref "C276") (pin "1") (pinfunction "1_1") (pintype "passive"))
      (node (ref "C277") (pin "1") (pinfunction "1_1") (pintype "passive"))
      (node (ref "R138") (pin "1") (pinfunction "1_1") (pintype "passive"))
      (node (ref "U17") (pin "2") (pinfunction "Vout_2") (pintype "passive"))
      (node (ref "U8") (pin "J10") (pinfunction "VCCINT_J10") (pintype "power_in"))
      (node (ref "U8") (pin "J12") (pinfunction "VCCINT_J12") (pintype "power_in"))
      (node (ref "U8") (pin "J14") (pinfunction "VCCINT_J14") (pintype "power_in"))
      (node (ref "U8") (pin "J8") (pinfunction "VCCINT_J8") (pintype "power_in"))
      (node (ref "U8") (pin "K11") (pinfunction "VCCINT_K11") (pintype "power_in"))
      (node (ref "U8") (pin "K13") (pinfunction "VCCINT_K13") (pintype "power_in"))
      (node (ref "U8") (pin "K9") (pinfunction "VCCINT_K9") (pintype "power_in"))
      (node (ref "U8") (pin "L10") (pinfunction "VCCINT_L10") (pintype "power_in"))
      (node (ref "U8") (pin "L12") (pinfunction "VCCINT_L12") (pintype "power_in"))
      (node (ref "U8") (pin "L14") (pinfunction "VCCINT_L14") (pintype "power_in"))
      (node (ref "U8") (pin "M11") (pinfunction "VCCINT_M11") (pintype "power_in"))
      (node (ref "U8") (pin "M13") (pinfunction "VCCINT_M13") (pintype "power_in"))
      (node (ref "U8") (pin "M9") (pinfunction "VCCINT_M9") (pintype "power_in"))
      (node (ref "U8") (pin "N10") (pinfunction "VCCINT_N10") (pintype "power_in"))
      (node (ref "U8") (pin "N12") (pinfunction "VCCINT_N12") (pintype "power_in"))
      (node (ref "U8") (pin "N14") (pinfunction "VCCINT_N14") (pintype "power_in"))
      (node (ref "U8") (pin "P11") (pinfunction "VCCINT_P11") (pintype "power_in"))
      (node (ref "U8") (pin "P13") (pinfunction "VCCINT_P13") (pintype "power_in"))
      (node (ref "U8") (pin "P9") (pinfunction "VCCINT_P9") (pintype "power_in"))
      (node (ref "U8") (pin "R14") (pinfunction "VCCINT_R14") (pintype "power_in"))
    )
    (net (code "2") (name "+2,5VETH") (class "Default")
      (node (ref "C157") (pin "1") (pinfunction "1_1") (pintype "passive"))
      (node (ref "C163") (pin "1") (pinfunction "1_1") (pintype "passive"))
      (node (ref "C171") (pin "1") (pinfunction "+_1") (pintype "passive"))
      (node (ref "C228") (pin "2") (pinfunction "2_2") (pintype "passive"))
      (node (ref "C229") (pin "1") (pinfunction "1_1") (pintype "passive"))
      (node (ref "C230") (pin "1") (pinfunction "1_1") (pintype "passive"))
      (node (ref "C231") (pin "1") (pinfunction "1_1") (pintype "passive"))
      (node (ref "C232") (pin "1") (pinfunction "1_1") (pintype "passive"))
      (node (ref "C233") (pin "1") (pinfunction "1_1") (pintype "passive"))
      (node (ref "C234") (pin "1") (pinfunction "1_1") (pintype "passive"))
      (node (ref "C235") (pin "1") (pinfunction "1_1") (pintype "passive"))
      (node (ref "L42") (pin "2") (pinfunction "2_2") (pintype "passive"))
      (node (ref "L45") (pin "1") (pinfunction "1_1") (pintype "passive"))
      (node (ref "Q3") (pin "3") (pinfunction "E_3") (pintype "passive"))
      (node (ref "U9") (pin "4") (pinfunction "DVDD_IO_4") (pintype "power_in"))
      (node (ref "U9") (pin "45") (pinfunction "VDD_REG_45") (pintype "passive"))
      (node (ref "U9") (pin "52") (pinfunction "DVDD_IO_52") (pintype "power_in"))
      (node (ref "U9") (pin "58") (pinfunction "DVDD_IO_58") (pintype "power_in"))
      (node (ref "U9") (pin "64") (pinfunction "DVDD_IO_64") (pintype "power_in"))
      (node (ref "U9") (pin "71") (pinfunction "DVDD_IO_71") (pintype "power_in"))
      (node (ref "U9") (pin "76") (pinfunction "DVDD_IO_76") (pintype "power_in"))
    )
    (net (code "3") (name "+2,5VFPGA") (class "Default")
      (node (ref "C156") (pin "1") (pinfunction "1_1") (pintype "passive"))
      (node (ref "C162") (pin "1") (pinfunction "1_1") (pintype "passive"))
      (node (ref "C166") (pin "1") (pinfunction "+_1") (pintype "passive"))
      (node (ref "C172") (pin "2") (pinfunction "2_2") (pintype "passive"))
      (node (ref "C175") (pin "2") (pinfunction "2_2") (pintype "passive"))
      (node (ref "C176") (pin "2") (pinfunction "2_2") (pintype "passive"))
      (node (ref "C177") (pin "2") (pinfunction "2_2") (pintype "passive"))
      (node (ref "C178") (pin "2") (pinfunction "2_2") (pintype "passive"))
      (node (ref "C179") (pin "2") (pinfunction "2_2") (pintype "passive"))
      (node (ref "C180") (pin "2") (pinfunction "2_2") (pintype "passive"))
      (node (ref "C181") (pin "2") (pinfunction "2_2") (pintype "passive"))
      (node (ref "C182") (pin "2") (pinfunction "2_2") (pintype "passive"))
      (node (ref "C183") (pin "2") (pinfunction "2_2") (pintype "passive"))
      (node (ref "C184") (pin "2") (pinfunction "2_2") (pintype "passive"))
      (node (ref "C185") (pin "2") (pinfunction "2_2") (pintype "passive"))
      (node (ref "C186") (pin "2") (pinfunction "2_2") (pintype "passive"))
      (node (ref "C187") (pin "2") (pinfunction "2_2") (pintype "passive"))
      (node (ref "C188") (pin "2") (pinfunction "2_2") (pintype "passive"))
      (node (ref "C189") (pin "2") (pinfunction "2_2") (pintype "passive"))
      (node (ref "C190") (pin "2") (pinfunction "2_2") (pintype "passive"))
      (node (ref "C191") (pin "2") (pinfunction "2_2") (pintype "passive"))
      (node (ref "C192") (pin "2") (pinfunction "2_2") (pintype "passive"))
      (node (ref "C193") (pin "2") (pinfunction "2_2") (pintype "passive"))
      (node (ref "C204") (pin "2") (pinfunction "2_2") (pintype "passive"))
      (node (ref "C205") (pin "2") (pinfunction "2_2") (pintype "passive"))
      (node (ref "C206") (pin "2") (pinfunction "2_2") (pintype "passive"))
      (node (ref "C207") (pin "2") (pinfunction "2_2") (pintype "passive"))
      (node (ref "C208") (pin "2") (pinfunction "2_2") (pintype "passive"))
      (node (ref "C209") (pin "2") (pinfunction "2_2") (pintype "passive"))
      (node (ref "C210") (pin "2") (pinfunction "2_2") (pintype "passive"))
      (node (ref "C211") (pin "2") (pinfunction "2_2") (pintype "passive"))
      (node (ref "C212") (pin "2") (pinfunction "2_2") (pintype "passive"))
      (node (ref "C213") (pin "2") (pinfunction "2_2") (pintype "passive"))
      (node (ref "L41") (pin "2") (pinfunction "2_2") (pintype "passive"))
      (node (ref "U8") (pin "B11") (pinfunction "VCCO_0_B11") (pintype "power_in"))
      (node (ref "U8") (pin "B15") (pinfunction "VCCO_0_B15") (pintype "power_in"))
      (node (ref "U8") (pin "B19") (pinfunction "VCCO_0_B19") (pintype "power_in"))
      (node (ref "U8") (pin "B4") (pinfunction "VCCO_0_B4") (pintype "power_in"))
      (node (ref "U8") (pin "B7") (pinfunction "VCCO_0_B7") (pintype "power_in"))
      (node (ref "U8") (pin "C2") (pinfunction "VCCO_3_C2") (pintype "power_in"))
      (node (ref "U8") (pin "C21") (pinfunction "VCCO_1_C21") (pintype "power_in"))
      (node (ref "U8") (pin "E13") (pinfunction "VCCO_0_E13") (pintype "power_in"))
      (node (ref "U8") (pin "E17") (pinfunction "VCCO_0_E17") (pintype "power_in"))
      (node (ref "U8") (pin "E19") (pinfunction "VCCO_1_E19") (pintype "power_in"))
      (node (ref "U8") (pin "E9") (pinfunction "VCCO_0_E9") (pintype "power_in"))
      (node (ref "U8") (pin "F4") (pinfunction "VCCO_3_F4") (pintype "power_in"))
      (node (ref "U8") (pin "F6") (pinfunction "VCCO_3_F6") (pintype "power_in"))
      (node (ref "U8") (pin "G10") (pinfunction "VCCO_0_G10") (pintype "power_in"))
      (node (ref "U8") (pin "G14") (pinfunction "VCCO_0_G14") (pintype "power_in"))
      (node (ref "U8") (pin "G2") (pinfunction "VCCO_3_G2") (pintype "power_in"))
      (node (ref "U8") (pin "G21") (pinfunction "VCCO_1_G21") (pintype "power_in"))
      (node (ref "U8") (pin "J18") (pinfunction "VCCO_1_J18") (pintype "power_in"))
      (node (ref "U8") (pin "J5") (pinfunction "VCCO_3_J5") (pintype "power_in"))
      (node (ref "U8") (pin "L16") (pinfunction "VCCO_1_L16") (pintype "power_in"))
      (node (ref "U8") (pin "L2") (pinfunction "VCCO_3_L2") (pintype "power_in"))
      (node (ref "U8") (pin "L21") (pinfunction "VCCO_1_L21") (pintype "power_in"))
      (node (ref "U8") (pin "L7") (pinfunction "VCCO_3_L7") (pintype "power_in"))
      (node (ref "U8") (pin "N18") (pinfunction "VCCO_1_N18") (pintype "power_in"))
      (node (ref "U8") (pin "N5") (pinfunction "VCCO_3_N5") (pintype "power_in"))
      (node (ref "U8") (pin "R2") (pinfunction "VCCO_3_R2") (pintype "power_in"))
      (node (ref "U8") (pin "R21") (pinfunction "VCCO_1_R21") (pintype "power_in"))
      (node (ref "U8") (pin "U18") (pinfunction "VCCO_1_U18") (pintype "power_in"))
      (node (ref "U8") (pin "U5") (pinfunction "VCCO_3_U5") (pintype "power_in"))
      (node (ref "U8") (pin "W2") (pinfunction "VCCO_3_W2") (pintype "power_in"))
      (node (ref "U8") (pin "W21") (pinfunction "VCCO_1_W21") (pintype "power_in"))
    )
    (net (code "4") (name "+2,5VRAM") (class "Default")
      (node (ref "C158") (pin "1") (pinfunction "1_1") (pintype "passive"))
      (node (ref "C164") (pin "1") (pinfunction "1_1") (pintype "passive"))
      (node (ref "C168") (pin "1") (pinfunction "+_1") (pintype "passive"))
      (node (ref "C215") (pin "2") (pinfunction "2_2") (pintype "passive"))
      (node (ref "C216") (pin "2") (pinfunction "2_2") (pintype "passive"))
      (node (ref "C217") (pin "2") (pinfunction "2_2") (pintype "passive"))
      (node (ref "C218") (pin "2") (pinfunction "2_2") (pintype "passive"))
      (node (ref "C219") (pin "2") (pinfunction "2_2") (pintype "passive"))
      (node (ref "C220") (pin "2") (pinfunction "2_2") (pintype "passive"))
      (node (ref "C221") (pin "2") (pinfunction "2_2") (pintype "passive"))
      (node (ref "C222") (pin "2") (pinfunction "2_2") (pintype "passive"))
      (node (ref "L43") (pin "2") (pinfunction "2_2") (pintype "passive"))
      (node (ref "U11") (pin "11") (pinfunction "VDDQ_11") (pintype "passive"))
      (node (ref "U11") (pin "20") (pinfunction "VDDQ_20") (pintype "passive"))
      (node (ref "U11") (pin "27") (pinfunction "VDDQ_27") (pintype "passive"))
      (node (ref "U11") (pin "4") (pinfunction "VDDQ_4") (pintype "passive"))
      (node (ref "U11") (pin "54") (pinfunction "VDDQ_54") (pintype "passive"))
      (node (ref "U11") (pin "61") (pinfunction "VDDQ_61") (pintype "passive"))
      (node (ref "U11") (pin "70") (pinfunction "VDDQ_70") (pintype "passive"))
      (node (ref "U11") (pin "77") (pinfunction "VDDQ_77") (pintype "passive"))
    )
    (net (code "5") (name "+3,3V1") (class "Default")
      (node (ref "C136") (pin "1") (pinfunction "1_1") (pintype "passive"))
      (node (ref "C141") (pin "1") (pinfunction "+_1") (pintype "passive"))
      (node (ref "C147") (pin "1") (pinfunction "1_1") (pintype "passive"))
      (node (ref "C150") (pin "1") (pinfunction "1_1") (pintype "passive"))
      (node (ref "C279") (pin "1") (pinfunction "1_1") (pintype "passive"))
      (node (ref "L36") (pin "2") (pinfunction "2_2") (pintype "passive"))
      (node (ref "L40") (pin "1") (pinfunction "1_1") (pintype "passive"))
      (node (ref "R136") (pin "1") (pinfunction "1_1") (pintype "passive"))
      (node (ref "R173") (pin "1") (pinfunction "1_1") (pintype "passive"))
      (node (ref "R174") (pin "1") (pinfunction "1_1") (pintype "passive"))
      (node (ref "U35") (pin "2") (pinfunction "~{F_ON}_2") (pintype "passive"))
      (node (ref "U35") (pin "7") (pinfunction "VDD_7") (pintype "passive"))
    )
    (net (code "6") (name "+3,3VFPGA") (class "Default")
      (node (ref "C159") (pin "1") (pinfunction "1_1") (pintype "passive"))
      (node (ref "C161") (pin "1") (pinfunction "1_1") (pintype "passive"))
      (node (ref "C165") (pin "1") (pinfunction "+_1") (pintype "passive"))
      (node (ref "C174") (pin "2") (pinfunction "2_2") (pintype "passive"))
      (node (ref "C194") (pin "2") (pinfunction "2_2") (pintype "passive"))
      (node (ref "C196") (pin "2") (pinfunction "2_2") (pintype "passive"))
      (node (ref "C197") (pin "2") (pinfunction "2_2") (pintype "passive"))
      (node (ref "C198") (pin "2") (pinfunction "2_2") (pintype "passive"))
      (node (ref "C199") (pin "2") (pinfunction "2_2") (pintype "passive"))
      (node (ref "C200") (pin "2") (pinfunction "2_2") (pintype "passive"))
      (node (ref "C201") (pin "2") (pinfunction "2_2") (pintype "passive"))
      (node (ref "C202") (pin "2") (pinfunction "2_2") (pintype "passive"))
      (node (ref "C203") (pin "2") (pinfunction "2_2") (pintype "passive"))
      (node (ref "C223") (pin "2") (pinfunction "2_2") (pintype "passive"))
      (node (ref "C224") (pin "2") (pinfunction "2_2") (pintype "passive"))
      (node (ref "C225") (pin "2") (pinfunction "2_2") (pintype "passive"))
      (node (ref "C227") (pin "2") (pinfunction "2_2") (pintype "passive"))
      (node (ref "C246") (pin "1") (pinfunction "1_1") (pintype "passive"))
      (node (ref "C247") (pin "1") (pinfunction "1_1") (pintype "passive"))
      (node (ref "C248") (pin "1") (pinfunction "1_1") (pintype "passive"))
      (node (ref "C249") (pin "1") (pinfunction "1_1") (pintype "passive"))
      (node (ref "C250") (pin "1") (pinfunction "1_1") (pintype "passive"))
      (node (ref "C251") (pin "1") (pinfunction "1_1") (pintype "passive"))
      (node (ref "C252") (pin "1") (pinfunction "1_1") (pintype "passive"))
      (node (ref "C254") (pin "1") (pinfunction "1_1") (pintype "passive"))
      (node (ref "C255") (pin "1") (pinfunction "1_1") (pintype "passive"))
      (node (ref "C256") (pin "1") (pinfunction "1_1") (pintype "passive"))
      (node (ref "C257") (pin "1") (pinfunction "1_1") (pintype "passive"))
      (node (ref "C258") (pin "1") (pinfunction "1_1") (pintype "passive"))
      (node (ref "C259") (pin "1") (pinfunction "1_1") (pintype "passive"))
      (node (ref "L40") (pin "2") (pinfunction "2_2") (pintype "passive"))
      (node (ref "U11") (pin "15") (pinfunction "VDD_15") (pintype "passive"))
      (node (ref "U11") (pin "41") (pinfunction "VDD_41") (pintype "passive"))
      (node (ref "U11") (pin "65") (pinfunction "VDD_65") (pintype "passive"))
      (node (ref "U11") (pin "91") (pinfunction "VDD_91") (pintype "passive"))
      (node (ref "U8") (pin "AA11") (pinfunction "VCCO_2_AA11") (pintype "power_in"))
      (node (ref "U8") (pin "AA15") (pinfunction "VCCO_2_AA15") (pintype "power_in"))
      (node (ref "U8") (pin "AA19") (pinfunction "VCCO_2_AA19") (pintype "power_in"))
      (node (ref "U8") (pin "AA3") (pinfunction "VCCO_2_AA3") (pintype "power_in"))
      (node (ref "U8") (pin "AA7") (pinfunction "VCCO_2_AA7") (pintype "power_in"))
      (node (ref "U8") (pin "D16") (pinfunction "VCCAUX_D16") (pintype "power_in"))
      (node (ref "U8") (pin "F11") (pinfunction "VCCAUX_F11") (pintype "power_in"))
      (node (ref "U8") (pin "G12") (pinfunction "VCCAUX_G12") (pintype "power_in"))
      (node (ref "U8") (pin "H15") (pinfunction "VCCAUX_H15") (pintype "power_in"))
      (node (ref "U8") (pin "H9") (pinfunction "VCCAUX_H9") (pintype "power_in"))
      (node (ref "U8") (pin "K15") (pinfunction "VCCAUX_K15") (pintype "power_in"))
      (node (ref "U8") (pin "L8") (pinfunction "VCCAUX_L8") (pintype "power_in"))
      (node (ref "U8") (pin "M15") (pinfunction "VCCAUX_M15") (pintype "power_in"))
      (node (ref "U8") (pin "N8") (pinfunction "VCCAUX_N8") (pintype "power_in"))
      (node (ref "U8") (pin "R10") (pinfunction "VCCAUX_R10") (pintype "power_in"))
      (node (ref "U8") (pin "R12") (pinfunction "VCCAUX_R12") (pintype "power_in"))
      (node (ref "U8") (pin "R17") (pinfunction "VBATT_R17") (pintype "power_in"))
      (node (ref "U8") (pin "R6") (pinfunction "VCCAUX_R6") (pintype "power_in"))
      (node (ref "U8") (pin "T13") (pinfunction "VCCO_2_T13") (pintype "power_in"))
      (node (ref "U8") (pin "T9") (pinfunction "VCCO_2_T9") (pintype "power_in"))
      (node (ref "U8") (pin "U11") (pinfunction "VCCAUX_U11") (pintype "power_in"))
      (node (ref "U8") (pin "V12") (pinfunction "VCCO_2_V12") (pintype "power_in"))
      (node (ref "U8") (pin "V16") (pinfunction "VCCO_2_V16") (pintype "power_in"))
      (node (ref "U8") (pin "V6") (pinfunction "VCCAUX_V6") (pintype "power_in"))
      (node (ref "U8") (pin "V8") (pinfunction "VCCO_2_V8") (pintype "power_in"))
      (node (ref "U8") (pin "W5") (pinfunction "VCCO_2_W5") (pintype "power_in"))
    )
    (net (code "7") (name "+6V") (class "Default")
      (node (ref "C125") (pin "1") (pinfunction "+_1") (pintype "passive"))
      (node (ref "L44") (pin "2") (pinfunction "2_2") (pintype "passive"))
    )
    (net (code "8") (name "+6V1") (class "Default")
      (node (ref "C113") (pin "1") (pinfunction "1_1") (pintype "passive"))
      (node (ref "C131") (pin "1") (pinfunction "+_1") (pintype "passive"))
      (node (ref "C261") (pin "1") (pinfunction "1_1") (pintype "passive"))
      (node (ref "C269") (pin "1") (pinfunction "1_1") (pintype "passive"))
      (node (ref "L35") (pin "2") (pinfunction "2_2") (pintype "passive"))
      (node (ref "L44") (pin "1") (pinfunction "1_1") (pintype "passive"))
      (node (ref "R170") (pin "1") (pinfunction "1_1") (pintype "passive"))
      (node (ref "R172") (pin "1") (pinfunction "1_1") (pintype "passive"))
      (node (ref "R172'") (pin "1") (pinfunction "1_1") (pintype "passive"))
    )
    (net (code "9") (name "+12V") (class "Default")
      (node (ref "C114") (pin "1") (pinfunction "1_1") (pintype "passive"))
      (node (ref "C115") (pin "1") (pinfunction "1_1") (pintype "passive"))
      (node (ref "C116") (pin "1") (pinfunction "1_1") (pintype "passive"))
      (node (ref "C117") (pin "1") (pinfunction "1_1") (pintype "passive"))
      (node (ref "C118") (pin "1") (pinfunction "1_1") (pintype "passive"))
      (node (ref "C119") (pin "1") (pinfunction "1_1") (pintype "passive"))
      (node (ref "D4") (pin "2") (pinfunction "C_2") (pintype "passive"))
      (node (ref "F1") (pin "2") (pinfunction "2_2") (pintype "passive"))
      (node (ref "R171") (pin "1") (pinfunction "1_1") (pintype "passive"))
      (node (ref "R171'") (pin "1") (pinfunction "1_1") (pintype "passive"))
      (node (ref "U15") (pin "8") (pinfunction "Vcc_8") (pintype "passive"))
      (node (ref "U16") (pin "8") (pinfunction "Vcc_8") (pintype "passive"))
      (node (ref "U34") (pin "8") (pinfunction "Vcc_8") (pintype "passive"))
    )
    (net (code "10") (name "/FAN_ON") (class "Default")
      (node (ref "U35") (pin "4") (pinfunction "FanOn_4") (pintype "passive"))
    )
    (net (code "11") (name "/INHIBIT") (class "Default")
      (node (ref "Q4") (pin "3") (pinfunction "C_3") (pintype "passive"))
      (node (ref "U16") (pin "3") (pinfunction "INH_3") (pintype "passive"))
      (node (ref "U34") (pin "3") (pinfunction "INH_3") (pintype "passive"))
    )
    (net (code "12") (name "/OVERHEAT") (class "Default")
      (node (ref "R173") (pin "2") (pinfunction "2_2") (pintype "passive"))
      (node (ref "U35") (pin "6") (pinfunction "~{WRN}_6") (pintype "passive"))
    )
    (net (code "13") (name "GND") (class "Default")
      (node (ref "C113") (pin "2") (pinfunction "2_2") (pintype "passive"))
      (node (ref "C114") (pin "2") (pinfunction "2_2") (pintype "passive"))
      (node (ref "C115") (pin "2") (pinfunction "2_2") (pintype "passive"))
      (node (ref "C116") (pin "2") (pinfunction "2_2") (pintype "passive"))
      (node (ref "C117") (pin "2") (pinfunction "2_2") (pintype "passive"))
      (node (ref "C118") (pin "2") (pinfunction "2_2") (pintype "passive"))
      (node (ref "C119") (pin "2") (pinfunction "2_2") (pintype "passive"))
      (node (ref "C120") (pin "2") (pinfunction "2_2") (pintype "passive"))
      (node (ref "C125") (pin "2") (pinfunction "-_2") (pintype "passive"))
      (node (ref "C128") (pin "2") (pinfunction "2_2") (pintype "passive"))
      (node (ref "C129") (pin "2") (pinfunction "2_2") (pintype "passive"))
      (node (ref "C131") (pin "2") (pinfunction "-_2") (pintype "passive"))
      (node (ref "C136") (pin "2") (pinfunction "2_2") (pintype "passive"))
      (node (ref "C137") (pin "2") (pinfunction "2_2") (pintype "passive"))
      (node (ref "C138") (pin "2") (pinfunction "-_2") (pintype "passive"))
      (node (ref "C140") (pin "2") (pinfunction "-_2") (pintype "passive"))
      (node (ref "C141") (pin "2") (pinfunction "-_2") (pintype "passive"))
      (node (ref "C143") (pin "2") (pinfunction "2_2") (pintype "passive"))
      (node (ref "C144") (pin "2") (pinfunction "2_2") (pintype "passive"))
      (node (ref "C145") (pin "2") (pinfunction "2_2") (pintype "passive"))
      (node (ref "C147") (pin "2") (pinfunction "2_2") (pintype "passive"))
      (node (ref "C148") (pin "2") (pinfunction "2_2") (pintype "passive"))
      (node (ref "C150") (pin "2") (pinfunction "2_2") (pintype "passive"))
      (node (ref "C151") (pin "2") (pinfunction "2_2") (pintype "passive"))
      (node (ref "C152") (pin "2") (pinfunction "2_2") (pintype "passive"))
      (node (ref "C153") (pin "2") (pinfunction "2_2") (pintype "passive"))
      (node (ref "C154") (pin "2") (pinfunction "2_2") (pintype "passive"))
      (node (ref "C156") (pin "2") (pinfunction "2_2") (pintype "passive"))
      (node (ref "C157") (pin "2") (pinfunction "2_2") (pintype "passive"))
      (node (ref "C158") (pin "2") (pinfunction "2_2") (pintype "passive"))
      (node (ref "C159") (pin "2") (pinfunction "2_2") (pintype "passive"))
      (node (ref "C161") (pin "2") (pinfunction "2_2") (pintype "passive"))
      (node (ref "C162") (pin "2") (pinfunction "2_2") (pintype "passive"))
      (node (ref "C163") (pin "2") (pinfunction "2_2") (pintype "passive"))
      (node (ref "C164") (pin "2") (pinfunction "2_2") (pintype "passive"))
      (node (ref "C165") (pin "2") (pinfunction "-_2") (pintype "passive"))
      (node (ref "C166") (pin "2") (pinfunction "-_2") (pintype "passive"))
      (node (ref "C168") (pin "2") (pinfunction "-_2") (pintype "passive"))
      (node (ref "C171") (pin "2") (pinfunction "-_2") (pintype "passive"))
      (node (ref "C172") (pin "1") (pinfunction "1_1") (pintype "passive"))
      (node (ref "C174") (pin "1") (pinfunction "1_1") (pintype "passive"))
      (node (ref "C175") (pin "1") (pinfunction "1_1") (pintype "passive"))
      (node (ref "C176") (pin "1") (pinfunction "1_1") (pintype "passive"))
      (node (ref "C177") (pin "1") (pinfunction "1_1") (pintype "passive"))
      (node (ref "C178") (pin "1") (pinfunction "1_1") (pintype "passive"))
      (node (ref "C179") (pin "1") (pinfunction "1_1") (pintype "passive"))
      (node (ref "C180") (pin "1") (pinfunction "1_1") (pintype "passive"))
      (node (ref "C181") (pin "1") (pinfunction "1_1") (pintype "passive"))
      (node (ref "C182") (pin "1") (pinfunction "1_1") (pintype "passive"))
      (node (ref "C183") (pin "1") (pinfunction "1_1") (pintype "passive"))
      (node (ref "C184") (pin "1") (pinfunction "1_1") (pintype "passive"))
      (node (ref "C185") (pin "1") (pinfunction "1_1") (pintype "passive"))
      (node (ref "C186") (pin "1") (pinfunction "1_1") (pintype "passive"))
      (node (ref "C187") (pin "1") (pinfunction "1_1") (pintype "passive"))
      (node (ref "C188") (pin "1") (pinfunction "1_1") (pintype "passive"))
      (node (ref "C189") (pin "1") (pinfunction "1_1") (pintype "passive"))
      (node (ref "C190") (pin "1") (pinfunction "1_1") (pintype "passive"))
      (node (ref "C191") (pin "1") (pinfunction "1_1") (pintype "passive"))
      (node (ref "C192") (pin "1") (pinfunction "1_1") (pintype "passive"))
      (node (ref "C193") (pin "1") (pinfunction "1_1") (pintype "passive"))
      (node (ref "C194") (pin "1") (pinfunction "1_1") (pintype "passive"))
      (node (ref "C196") (pin "1") (pinfunction "1_1") (pintype "passive"))
      (node (ref "C197") (pin "1") (pinfunction "1_1") (pintype "passive"))
      (node (ref "C198") (pin "1") (pinfunction "1_1") (pintype "passive"))
      (node (ref "C199") (pin "1") (pinfunction "1_1") (pintype "passive"))
      (node (ref "C200") (pin "1") (pinfunction "1_1") (pintype "passive"))
      (node (ref "C201") (pin "1") (pinfunction "1_1") (pintype "passive"))
      (node (ref "C202") (pin "1") (pinfunction "1_1") (pintype "passive"))
      (node (ref "C203") (pin "1") (pinfunction "1_1") (pintype "passive"))
      (node (ref "C204") (pin "1") (pinfunction "1_1") (pintype "passive"))
      (node (ref "C205") (pin "1") (pinfunction "1_1") (pintype "passive"))
      (node (ref "C206") (pin "1") (pinfunction "1_1") (pintype "passive"))
      (node (ref "C207") (pin "1") (pinfunction "1_1") (pintype "passive"))
      (node (ref "C208") (pin "1") (pinfunction "1_1") (pintype "passive"))
      (node (ref "C209") (pin "1") (pinfunction "1_1") (pintype "passive"))
      (node (ref "C210") (pin "1") (pinfunction "1_1") (pintype "passive"))
      (node (ref "C211") (pin "1") (pinfunction "1_1") (pintype "passive"))
      (node (ref "C212") (pin "1") (pinfunction "1_1") (pintype "passive"))
      (node (ref "C213") (pin "1") (pinfunction "1_1") (pintype "passive"))
      (node (ref "C214") (pin "1") (pinfunction "1_1") (pintype "passive"))
      (node (ref "C215") (pin "1") (pinfunction "1_1") (pintype "passive"))
      (node (ref "C216") (pin "1") (pinfunction "1_1") (pintype "passive"))
      (node (ref "C217") (pin "1") (pinfunction "1_1") (pintype "passive"))
      (node (ref "C218") (pin "1") (pinfunction "1_1") (pintype "passive"))
      (node (ref "C219") (pin "1") (pinfunction "1_1") (pintype "passive"))
      (node (ref "C220") (pin "1") (pinfunction "1_1") (pintype "passive"))
      (node (ref "C221") (pin "1") (pinfunction "1_1") (pintype "passive"))
      (node (ref "C222") (pin "1") (pinfunction "1_1") (pintype "passive"))
      (node (ref "C223") (pin "1") (pinfunction "1_1") (pintype "passive"))
      (node (ref "C224") (pin "1") (pinfunction "1_1") (pintype "passive"))
      (node (ref "C225") (pin "1") (pinfunction "1_1") (pintype "passive"))
      (node (ref "C227") (pin "1") (pinfunction "1_1") (pintype "passive"))
      (node (ref "C228") (pin "1") (pinfunction "1_1") (pintype "passive"))
      (node (ref "C229") (pin "2") (pinfunction "2_2") (pintype "passive"))
      (node (ref "C23") (pin "2") (pinfunction "2_2") (pintype "passive"))
      (node (ref "C230") (pin "2") (pinfunction "2_2") (pintype "passive"))
      (node (ref "C231") (pin "2") (pinfunction "2_2") (pintype "passive"))
      (node (ref "C232") (pin "2") (pinfunction "2_2") (pintype "passive"))
      (node (ref "C233") (pin "2") (pinfunction "2_2") (pintype "passive"))
      (node (ref "C234") (pin "2") (pinfunction "2_2") (pintype "passive"))
      (node (ref "C235") (pin "2") (pinfunction "2_2") (pintype "passive"))
      (node (ref "C236") (pin "2") (pinfunction "2_2") (pintype "passive"))
      (node (ref "C237") (pin "2") (pinfunction "2_2") (pintype "passive"))
      (node (ref "C238") (pin "2") (pinfunction "2_2") (pintype "passive"))
      (node (ref "C239") (pin "2") (pinfunction "2_2") (pintype "passive"))
      (node (ref "C240") (pin "2") (pinfunction "2_2") (pintype "passive"))
      (node (ref "C241") (pin "2") (pinfunction "2_2") (pintype "passive"))
      (node (ref "C242") (pin "2") (pinfunction "2_2") (pintype "passive"))
      (node (ref "C243") (pin "2") (pinfunction "2_2") (pintype "passive"))
      (node (ref "C244") (pin "2") (pinfunction "2_2") (pintype "passive"))
      (node (ref "C245") (pin "2") (pinfunction "2_2") (pintype "passive"))
      (node (ref "C246") (pin "2") (pinfunction "2_2") (pintype "passive"))
      (node (ref "C247") (pin "2") (pinfunction "2_2") (pintype "passive"))
      (node (ref "C248") (pin "2") (pinfunction "2_2") (pintype "passive"))
      (node (ref "C249") (pin "2") (pinfunction "2_2") (pintype "passive"))
      (node (ref "C250") (pin "2") (pinfunction "2_2") (pintype "passive"))
      (node (ref "C251") (pin "2") (pinfunction "2_2") (pintype "passive"))
      (node (ref "C252") (pin "2") (pinfunction "2_2") (pintype "passive"))
      (node (ref "C254") (pin "2") (pinfunction "2_2") (pintype "passive"))
      (node (ref "C255") (pin "2") (pinfunction "2_2") (pintype "passive"))
      (node (ref "C256") (pin "2") (pinfunction "2_2") (pintype "passive"))
      (node (ref "C257") (pin "2") (pinfunction "2_2") (pintype "passive"))
      (node (ref "C258") (pin "2") (pinfunction "2_2") (pintype "passive"))
      (node (ref "C259") (pin "2") (pinfunction "2_2") (pintype "passive"))
      (node (ref "C260") (pin "2") (pinfunction "2_2") (pintype "passive"))
      (node (ref "C261") (pin "2") (pinfunction "2_2") (pintype "passive"))
      (node (ref "C262") (pin "2") (pinfunction "2_2") (pintype "passive"))
      (node (ref "C263") (pin "2") (pinfunction "2_2") (pintype "passive"))
      (node (ref "C264") (pin "2") (pinfunction "2_2") (pintype "passive"))
      (node (ref "C265") (pin "2") (pinfunction "2_2") (pintype "passive"))
      (node (ref "C266") (pin "2") (pinfunction "2_2") (pintype "passive"))
      (node (ref "C268") (pin "2") (pinfunction "2_2") (pintype "passive"))
      (node (ref "C269") (pin "2") (pinfunction "2_2") (pintype "passive"))
      (node (ref "C270") (pin "2") (pinfunction "2_2") (pintype "passive"))
      (node (ref "C271") (pin "2") (pinfunction "2_2") (pintype "passive"))
      (node (ref "C272") (pin "2") (pinfunction "2_2") (pintype "passive"))
      (node (ref "C273") (pin "2") (pinfunction "2_2") (pintype "passive"))
      (node (ref "C274") (pin "2") (pinfunction "2_2") (pintype "passive"))
      (node (ref "C276") (pin "2") (pinfunction "2_2") (pintype "passive"))
      (node (ref "C277") (pin "2") (pinfunction "2_2") (pintype "passive"))
      (node (ref "C279") (pin "2") (pinfunction "2_2") (pintype "passive"))
      (node (ref "C280") (pin "2") (pinfunction "2_2") (pintype "passive"))
      (node (ref "C281") (pin "2") (pinfunction "2_2") (pintype "passive"))
      (node (ref "C282") (pin "2") (pinfunction "2_2") (pintype "passive"))
      (node (ref "C283") (pin "2") (pinfunction "2_2") (pintype "passive"))
      (node (ref "C284") (pin "2") (pinfunction "2_2") (pintype "passive"))
      (node (ref "C285") (pin "2") (pinfunction "2_2") (pintype "passive"))
      (node (ref "C286") (pin "1") (pinfunction "1_1") (pintype "passive"))
      (node (ref "C287") (pin "1") (pinfunction "1_1") (pintype "passive"))
      (node (ref "D1") (pin "2") (pinfunction "A_2") (pintype "passive"))
      (node (ref "D2") (pin "2") (pinfunction "A_2") (pintype "passive"))
      (node (ref "D3") (pin "2") (pinfunction "A_2") (pintype "passive"))
      (node (ref "D4") (pin "1") (pinfunction "A_1") (pintype "passive"))
      (node (ref "Q4") (pin "2") (pinfunction "E_2") (pintype "passive"))
      (node (ref "R128") (pin "1") (pinfunction "1_1") (pintype "passive"))
      (node (ref "R129") (pin "1") (pinfunction "1_1") (pintype "passive"))
      (node (ref "R131") (pin "2") (pinfunction "2_2") (pintype "passive"))
      (node (ref "R132") (pin "2") (pinfunction "2_2") (pintype "passive"))
      (node (ref "R138") (pin "2") (pinfunction "2_2") (pintype "passive"))
      (node (ref "R168") (pin "1") (pinfunction "1_1") (pintype "passive"))
      (node (ref "R169") (pin "2") (pinfunction "2_2") (pintype "passive"))
      (node (ref "U11") (pin "10") (pinfunction "VSS_10") (pintype "passive"))
      (node (ref "U11") (pin "17") (pinfunction "VSS_17") (pintype "passive"))
      (node (ref "U11") (pin "21") (pinfunction "VSS_21") (pintype "passive"))
      (node (ref "U11") (pin "26") (pinfunction "VSS_26") (pintype "passive"))
      (node (ref "U11") (pin "40") (pinfunction "VSS_40") (pintype "passive"))
      (node (ref "U11") (pin "5") (pinfunction "VSS_5") (pintype "passive"))
      (node (ref "U11") (pin "55") (pinfunction "VSS_55") (pintype "passive"))
      (node (ref "U11") (pin "60") (pinfunction "VSS_60") (pintype "passive"))
      (node (ref "U11") (pin "67") (pinfunction "VSS_67") (pintype "passive"))
      (node (ref "U11") (pin "71") (pinfunction "VSS_71") (pintype "passive"))
      (node (ref "U11") (pin "76") (pinfunction "VSS_76") (pintype "passive"))
      (node (ref "U11") (pin "90") (pinfunction "VSS_90") (pintype "passive"))
      (node (ref "U15") (pin "0") (pinfunction "GND_0") (pintype "passive"))
      (node (ref "U15") (pin "3") (pinfunction "INH_3") (pintype "passive"))
      (node (ref "U15") (pin "7") (pinfunction "GND_7") (pintype "power_in"))
      (node (ref "U16") (pin "0") (pinfunction "GND_0") (pintype "passive"))
      (node (ref "U16") (pin "7") (pinfunction "GND_7") (pintype "power_in"))
      (node (ref "U17") (pin "1") (pinfunction "ADJ_1") (pintype "passive"))
      (node (ref "U34") (pin "0") (pinfunction "GND_0") (pintype "passive"))
      (node (ref "U34") (pin "7") (pinfunction "GND_7") (pintype "power_in"))
      (node (ref "U35") (pin "1") (pinfunction "GND_1") (pintype "passive"))
      (node (ref "U35") (pin "3") (pinfunction "HYST_3") (pintype "passive"))
      (node (ref "U8") (pin "A1") (pinfunction "GND_A1") (pintype "power_in"))
      (node (ref "U8") (pin "A22") (pinfunction "GND_A22") (pintype "power_in"))
      (node (ref "U8") (pin "AA13") (pinfunction "GND_AA13") (pintype "power_in"))
      (node (ref "U8") (pin "AA17") (pinfunction "GND_AA17") (pintype "power_in"))
      (node (ref "U8") (pin "AA5") (pinfunction "GND_AA5") (pintype "power_in"))
      (node (ref "U8") (pin "AA9") (pinfunction "GND_AA9") (pintype "power_in"))
      (node (ref "U8") (pin "AB1") (pinfunction "GND_AB1") (pintype "power_in"))
      (node (ref "U8") (pin "AB22") (pinfunction "GND_AB22") (pintype "power_in"))
      (node (ref "U8") (pin "B13") (pinfunction "GND_B13") (pintype "power_in"))
      (node (ref "U8") (pin "B17") (pinfunction "GND_B17") (pintype "power_in"))
      (node (ref "U8") (pin "B5") (pinfunction "GND_B5") (pintype "power_in"))
      (node (ref "U8") (pin "B9") (pinfunction "GND_B9") (pintype "power_in"))
      (node (ref "U8") (pin "D18") (pinfunction "GND_D18") (pintype "power_in"))
      (node (ref "U8") (pin "D4") (pinfunction "GND_D4") (pintype "power_in"))
      (node (ref "U8") (pin "E11") (pinfunction "GND_E11") (pintype "power_in"))
      (node (ref "U8") (pin "E15") (pinfunction "GND_E15") (pintype "power_in"))
      (node (ref "U8") (pin "E2") (pinfunction "GND_E2") (pintype "power_in"))
      (node (ref "U8") (pin "E21") (pinfunction "GND_E21") (pintype "power_in"))
      (node (ref "U8") (pin "E7") (pinfunction "GND_E7") (pintype "power_in"))
      (node (ref "U8") (pin "G18") (pinfunction "GND_G18") (pintype "power_in"))
      (node (ref "U8") (pin "G5") (pinfunction "GND_G5") (pintype "power_in"))
      (node (ref "U8") (pin "H7") (pinfunction "GND_H7") (pintype "power_in"))
      (node (ref "U8") (pin "J11") (pinfunction "GND_J11") (pintype "power_in"))
      (node (ref "U8") (pin "J13") (pinfunction "GND_J13") (pintype "power_in"))
      (node (ref "U8") (pin "J15") (pinfunction "GND_J15") (pintype "power_in"))
      (node (ref "U8") (pin "J2") (pinfunction "GND_J2") (pintype "power_in"))
      (node (ref "U8") (pin "J21") (pinfunction "GND_J21") (pintype "power_in"))
      (node (ref "U8") (pin "J9") (pinfunction "GND_J9") (pintype "power_in"))
      (node (ref "U8") (pin "K10") (pinfunction "GND_K10") (pintype "power_in"))
      (node (ref "U8") (pin "K12") (pinfunction "GND_K12") (pintype "power_in"))
      (node (ref "U8") (pin "K14") (pinfunction "GND_K14") (pintype "power_in"))
      (node (ref "U8") (pin "L11") (pinfunction "GND_L11") (pintype "power_in"))
      (node (ref "U8") (pin "L13") (pinfunction "GND_L13") (pintype "power_in"))
      (node (ref "U8") (pin "L18") (pinfunction "GND_L18") (pintype "power_in"))
      (node (ref "U8") (pin "L5") (pinfunction "GND_L5") (pintype "power_in"))
      (node (ref "U8") (pin "L9") (pinfunction "GND_L9") (pintype "power_in"))
      (node (ref "U8") (pin "M10") (pinfunction "GND_M10") (pintype "power_in"))
      (node (ref "U8") (pin "M12") (pinfunction "GND_M12") (pintype "power_in"))
      (node (ref "U8") (pin "M14") (pinfunction "GND_M14") (pintype "power_in"))
      (node (ref "U8") (pin "N11") (pinfunction "GND_N11") (pintype "power_in"))
      (node (ref "U8") (pin "N13") (pinfunction "GND_N13") (pintype "power_in"))
      (node (ref "U8") (pin "N17") (pinfunction "GND_N17") (pintype "power_in"))
      (node (ref "U8") (pin "N2") (pinfunction "GND_N2") (pintype "power_in"))
      (node (ref "U8") (pin "N21") (pinfunction "GND_N21") (pintype "power_in"))
      (node (ref "U8") (pin "N9") (pinfunction "GND_N9") (pintype "power_in"))
      (node (ref "U8") (pin "P10") (pinfunction "GND_P10") (pintype "power_in"))
      (node (ref "U8") (pin "P12") (pinfunction "GND_P12") (pintype "power_in"))
      (node (ref "U8") (pin "P14") (pinfunction "GND_P14") (pintype "power_in"))
      (node (ref "U8") (pin "R18") (pinfunction "GND_R18") (pintype "power_in"))
      (node (ref "U8") (pin "R5") (pinfunction "GND_R5") (pintype "power_in"))
      (node (ref "U8") (pin "U2") (pinfunction "GND_U2") (pintype "power_in"))
      (node (ref "U8") (pin "U21") (pinfunction "GND_U21") (pintype "power_in"))
      (node (ref "U8") (pin "U7") (pinfunction "GND_U7") (pintype "power_in"))
      (node (ref "U8") (pin "V10") (pinfunction "GND_V10") (pintype "power_in"))
      (node (ref "U8") (pin "V14") (pinfunction "GND_V14") (pintype "power_in"))
      (node (ref "U8") (pin "V4") (pinfunction "GND_V4") (pintype "power_in"))
      (node (ref "U8") (pin "W16") (pinfunction "GND_W16") (pintype "power_in"))
      (node (ref "U8") (pin "W19") (pinfunction "GND_W19") (pintype "power_in"))
      (node (ref "U8") (pin "W7") (pinfunction "GND_W7") (pintype "power_in"))
      (node (ref "U9") (pin "0") (pinfunction "GND_PAD_0") (pintype "power_in"))
      (node (ref "X17") (pin "2") (pinfunction "2_2") (pintype "passive"))
      (node (ref "X5") (pin "2") (pinfunction "2_2") (pintype "passive"))
      (node (ref "X5'") (pin "2") (pinfunction "2_2") (pintype "passive"))
    )
    (net (code "14") (name "Net-(C132-Pad2)") (class "Default")
      (node (ref "C132") (pin "2") (pinfunction "2_2") (pintype "passive"))
      (node (ref "R131") (pin "1") (pinfunction "1_1") (pintype "passive"))
    )
    (net (code "15") (name "Net-(C133-Pad2)") (class "Default")
      (node (ref "C133") (pin "2") (pinfunction "2_2") (pintype "passive"))
      (node (ref "R132") (pin "1") (pinfunction "1_1") (pintype "passive"))
    )
    (net (code "16") (name "Net-(C140-+)") (class "Default")
      (node (ref "C137") (pin "1") (pinfunction "1_1") (pintype "passive"))
      (node (ref "C140") (pin "1") (pinfunction "+_1") (pintype "passive"))
      (node (ref "C143") (pin "1") (pinfunction "1_1") (pintype "passive"))
      (node (ref "C144") (pin "1") (pinfunction "1_1") (pintype "passive"))
      (node (ref "C145") (pin "1") (pinfunction "1_1") (pintype "passive"))
      (node (ref "C151") (pin "1") (pinfunction "1_1") (pintype "passive"))
      (node (ref "C152") (pin "1") (pinfunction "1_1") (pintype "passive"))
      (node (ref "C153") (pin "1") (pinfunction "1_1") (pintype "passive"))
      (node (ref "L37") (pin "2") (pinfunction "2_2") (pintype "passive"))
      (node (ref "L41") (pin "1") (pinfunction "1_1") (pintype "passive"))
      (node (ref "L42") (pin "1") (pinfunction "1_1") (pintype "passive"))
      (node (ref "L43") (pin "1") (pinfunction "1_1") (pintype "passive"))
      (node (ref "R133") (pin "1") (pinfunction "1_1") (pintype "passive"))
      (node (ref "R137") (pin "1") (pinfunction "1_1") (pintype "passive"))
    )
    (net (code "17") (name "Net-(C214-Pad2)") (class "Default")
      (node (ref "C214") (pin "2") (pinfunction "2_2") (pintype "passive"))
      (node (ref "C236") (pin "1") (pinfunction "1_1") (pintype "passive"))
      (node (ref "C237") (pin "1") (pinfunction "1_1") (pintype "passive"))
      (node (ref "C238") (pin "1") (pinfunction "1_1") (pintype "passive"))
      (node (ref "C239") (pin "1") (pinfunction "1_1") (pintype "passive"))
      (node (ref "C240") (pin "1") (pinfunction "1_1") (pintype "passive"))
      (node (ref "C241") (pin "1") (pinfunction "1_1") (pintype "passive"))
      (node (ref "C242") (pin "1") (pinfunction "1_1") (pintype "passive"))
      (node (ref "C243") (pin "1") (pinfunction "1_1") (pintype "passive"))
      (node (ref "C244") (pin "1") (pinfunction "1_1") (pintype "passive"))
      (node (ref "C245") (pin "1") (pinfunction "1_1") (pintype "passive"))
      (node (ref "C280") (pin "1") (pinfunction "1_1") (pintype "passive"))
      (node (ref "C284") (pin "1") (pinfunction "1_1") (pintype "passive"))
      (node (ref "C285") (pin "1") (pinfunction "1_1") (pintype "passive"))
      (node (ref "C286") (pin "2") (pinfunction "2_2") (pintype "passive"))
      (node (ref "C287") (pin "2") (pinfunction "2_2") (pintype "passive"))
      (node (ref "Q3") (pin "2") (pinfunction "C_2") (pintype "passive"))
      (node (ref "Q3") (pin "4") (pinfunction "C_4") (pintype "passive"))
      (node (ref "U9") (pin "19") (pinfunction "VDD_1V_19") (pintype "power_in"))
      (node (ref "U9") (pin "20") (pinfunction "AVDDL_1V_20") (pintype "power_in"))
      (node (ref "U9") (pin "27") (pinfunction "AVDDL_1V_27") (pintype "power_in"))
      (node (ref "U9") (pin "30") (pinfunction "AVDDL_1V_30") (pintype "power_in"))
      (node (ref "U9") (pin "33") (pinfunction "AVDDL_1V_33") (pintype "power_in"))
      (node (ref "U9") (pin "36") (pinfunction "AVDDL_1V_36") (pintype "power_in"))
      (node (ref "U9") (pin "39") (pinfunction "AVDDL_1V_39") (pintype "power_in"))
      (node (ref "U9") (pin "48") (pinfunction "VDD_1V_48") (pintype "power_in"))
      (node (ref "U9") (pin "56") (pinfunction "VDD_1V_56") (pintype "power_in"))
      (node (ref "U9") (pin "6") (pinfunction "VDD_1V_6") (pintype "power_in"))
      (node (ref "U9") (pin "63") (pinfunction "VDD_1V_63") (pintype "power_in"))
    )
    (net (code "18") (name "Net-(C267-Pad2)") (class "Default")
      (node (ref "C267") (pin "2") (pinfunction "2_2") (pintype "passive"))
      (node (ref "R169") (pin "1") (pinfunction "1_1") (pintype "passive"))
    )
    (net (code "19") (name "Net-(C281-Pad1)") (class "Default")
      (node (ref "C281") (pin "1") (pinfunction "1_1") (pintype "passive"))
      (node (ref "C282") (pin "1") (pinfunction "1_1") (pintype "passive"))
      (node (ref "C283") (pin "1") (pinfunction "1_1") (pintype "passive"))
      (node (ref "L45") (pin "2") (pinfunction "2_2") (pintype "passive"))
      (node (ref "U9") (pin "21") (pinfunction "AVDDH_2V5_21") (pintype "power_in"))
      (node (ref "U9") (pin "31") (pinfunction "AVDDH_2V5_31") (pintype "power_in"))
    )
    (net (code "20") (name "Net-(D1-C)") (class "Default")
      (node (ref "D1") (pin "1") (pinfunction "C_1") (pintype "passive"))
      (node (ref "L36") (pin "1") (pinfunction "1_1") (pintype "passive"))
      (node (ref "U15") (pin "1") (pinfunction "OUT_1") (pintype "output"))
    )
    (net (code "21") (name "Net-(D2-C)") (class "Default")
      (node (ref "D2") (pin "1") (pinfunction "C_1") (pintype "passive"))
      (node (ref "L37") (pin "1") (pinfunction "1_1") (pintype "passive"))
      (node (ref "U16") (pin "1") (pinfunction "OUT_1") (pintype "output"))
    )
    (net (code "22") (name "Net-(D3-C)") (class "Default")
      (node (ref "D3") (pin "1") (pinfunction "C_1") (pintype "passive"))
      (node (ref "L35") (pin "1") (pinfunction "1_1") (pintype "passive"))
      (node (ref "U34") (pin "1") (pinfunction "OUT_1") (pintype "output"))
    )
    (net (code "23") (name "Net-(F1-Pad1)") (class "Default")
      (node (ref "F1") (pin "1") (pinfunction "1_1") (pintype "passive"))
      (node (ref "X5") (pin "1") (pinfunction "1_1") (pintype "passive"))
      (node (ref "X5'") (pin "1") (pinfunction "1_1") (pintype "passive"))
    )
    (net (code "24") (name "Net-(Q3-B)") (class "Default")
      (node (ref "Q3") (pin "1") (pinfunction "B_1") (pintype "passive"))
      (node (ref "U9") (pin "47") (pinfunction "CTRL_1V0_47") (pintype "passive"))
    )
    (net (code "25") (name "Net-(Q4-B)") (class "Default")
      (node (ref "Q4") (pin "1") (pinfunction "B_1") (pintype "passive"))
      (node (ref "R174") (pin "2") (pinfunction "2_2") (pintype "passive"))
      (node (ref "U35") (pin "5") (pinfunction "~{OT}_5") (pintype "passive"))
    )
    (net (code "26") (name "Net-(R171'-Pad2)") (class "Default")
      (node (ref "R171'") (pin "2") (pinfunction "2_2") (pintype "passive"))
      (node (ref "R172'") (pin "2") (pinfunction "2_2") (pintype "passive"))
      (node (ref "X18") (pin "1") (pinfunction "1_1") (pintype "passive"))
    )
    (net (code "27") (name "Net-(R171-Pad2)") (class "Default")
      (node (ref "R171") (pin "2") (pinfunction "2_2") (pintype "passive"))
      (node (ref "R172") (pin "2") (pinfunction "2_2") (pintype "passive"))
      (node (ref "X17") (pin "1") (pinfunction "1_1") (pintype "passive"))
    )
    (net (code "28") (name "Net-(U15-COMP)") (class "Default")
      (node (ref "C128") (pin "1") (pinfunction "1_1") (pintype "passive"))
      (node (ref "C132") (pin "1") (pinfunction "1_1") (pintype "passive"))
      (node (ref "U15") (pin "4") (pinfunction "COMP_4") (pintype "passive"))
    )
    (net (code "29") (name "Net-(U15-FB)") (class "Default")
      (node (ref "R128") (pin "2") (pinfunction "2_2") (pintype "passive"))
      (node (ref "R136") (pin "2") (pinfunction "2_2") (pintype "passive"))
      (node (ref "U15") (pin "5") (pinfunction "FB_5") (pintype "passive"))
    )
    (net (code "30") (name "Net-(U15-SYNC)") (class "Default")
      (node (ref "C23") (pin "1") (pinfunction "1_1") (pintype "passive"))
      (node (ref "U15") (pin "2") (pinfunction "SYNC_2") (pintype "passive"))
      (node (ref "U16") (pin "2") (pinfunction "SYNC_2") (pintype "passive"))
      (node (ref "U34") (pin "2") (pinfunction "SYNC_2") (pintype "passive"))
    )
    (net (code "31") (name "Net-(U16-COMP)") (class "Default")
      (node (ref "C129") (pin "1") (pinfunction "1_1") (pintype "passive"))
      (node (ref "C133") (pin "1") (pinfunction "1_1") (pintype "passive"))
      (node (ref "U16") (pin "4") (pinfunction "COMP_4") (pintype "passive"))
    )
    (net (code "32") (name "Net-(U16-FB)") (class "Default")
      (node (ref "R129") (pin "2") (pinfunction "2_2") (pintype "passive"))
      (node (ref "R137") (pin "2") (pinfunction "2_2") (pintype "passive"))
      (node (ref "U16") (pin "5") (pinfunction "FB_5") (pintype "passive"))
    )
    (net (code "33") (name "Net-(U17-Vin)") (class "Default")
      (node (ref "C120") (pin "1") (pinfunction "1_1") (pintype "passive"))
      (node (ref "R133") (pin "2") (pinfunction "2_2") (pintype "passive"))
      (node (ref "U17") (pin "3") (pinfunction "Vin_3") (pintype "passive"))
    )
    (net (code "34") (name "Net-(U34-COMP)") (class "Default")
      (node (ref "C266") (pin "1") (pinfunction "1_1") (pintype "passive"))
      (node (ref "C267") (pin "1") (pinfunction "1_1") (pintype "passive"))
      (node (ref "U34") (pin "4") (pinfunction "COMP_4") (pintype "passive"))
    )
    (net (code "35") (name "Net-(U34-FB)") (class "Default")
      (node (ref "R168") (pin "2") (pinfunction "2_2") (pintype "passive"))
      (node (ref "R170") (pin "2") (pinfunction "2_2") (pintype "passive"))
      (node (ref "U34") (pin "5") (pinfunction "FB_5") (pintype "passive"))
    )
    (net (code "36") (name "Net-(U35-~{FAN}-)") (class "Default")
      (node (ref "U35") (pin "8") (pinfunction "~{FAN}-_8") (pintype "passive"))
      (node (ref "X18") (pin "2") (pinfunction "2_2") (pintype "passive"))
    )
    (net (code "37") (name "unconnected-(U8H-NC-PadAB5)") (class "Default")
      (node (ref "U8") (pin "AB5") (pinfunction "NC_AB5") (pintype "passive+no_connect"))
    )
    (net (code "38") (name "unconnected-(U8H-NC-PadE8)") (class "Default")
      (node (ref "U8") (pin "E8") (pinfunction "NC_E8") (pintype "passive+no_connect"))
    )
    (net (code "39") (name "unconnected-(U8H-NC-PadE10)") (class "Default")
      (node (ref "U8") (pin "E10") (pinfunction "NC_E10") (pintype "passive+no_connect"))
    )
    (net (code "40") (name "unconnected-(U8H-NC-PadF8)") (class "Default")
      (node (ref "U8") (pin "F8") (pinfunction "NC_F8") (pintype "passive+no_connect"))
    )
    (net (code "41") (name "unconnected-(U8H-NC-PadF9)") (class "Default")
      (node (ref "U8") (pin "F9") (pinfunction "NC_F9") (pintype "passive+no_connect"))
    )
    (net (code "42") (name "unconnected-(U8H-NC-PadF10)") (class "Default")
      (node (ref "U8") (pin "F10") (pinfunction "NC_F10") (pintype "passive+no_connect"))
    )
    (net (code "43") (name "unconnected-(U8H-NC-PadF12)") (class "Default")
      (node (ref "U8") (pin "F12") (pinfunction "NC_F12") (pintype "passive+no_connect"))
    )
    (net (code "44") (name "unconnected-(U8H-NC-PadG8)") (class "Default")
      (node (ref "U8") (pin "G8") (pinfunction "NC_G8") (pintype "passive+no_connect"))
    )
    (net (code "45") (name "unconnected-(U8H-NC-PadG9)") (class "Default")
      (node (ref "U8") (pin "G9") (pinfunction "NC_G9") (pintype "passive+no_connect"))
    )
    (net (code "46") (name "unconnected-(U8H-NC-PadG11)") (class "Default")
      (node (ref "U8") (pin "G11") (pinfunction "NC_G11") (pintype "passive+no_connect"))
    )
    (net (code "47") (name "unconnected-(U8H-NC-PadH10)") (class "Default")
      (node (ref "U8") (pin "H10") (pinfunction "NC_H10") (pintype "passive+no_connect"))
    )
    (net (code "48") (name "unconnected-(U8H-NC-PadH11)") (class "Default")
      (node (ref "U8") (pin "H11") (pinfunction "NC_H11") (pintype "passive+no_connect"))
    )
    (net (code "49") (name "unconnected-(U8H-NC-PadH12)") (class "Default")
      (node (ref "U8") (pin "H12") (pinfunction "NC_H12") (pintype "passive+no_connect"))
    )
    (net (code "50") (name "unconnected-(U8H-NC-PadR7)") (class "Default")
      (node (ref "U8") (pin "R7") (pinfunction "NC_R7") (pintype "passive+no_connect"))
    )
    (net (code "51") (name "unconnected-(U8H-NC-PadR8)") (class "Default")
      (node (ref "U8") (pin "R8") (pinfunction "NC_R8") (pintype "passive+no_connect"))
    )
    (net (code "52") (name "unconnected-(U8H-NC-PadR9)") (class "Default")
      (node (ref "U8") (pin "R9") (pinfunction "NC_R9") (pintype "passive+no_connect"))
    )
    (net (code "53") (name "unconnected-(U8H-NC-PadR11)") (class "Default")
      (node (ref "U8") (pin "R11") (pinfunction "NC_R11") (pintype "passive+no_connect"))
    )
    (net (code "54") (name "unconnected-(U8H-NC-PadR13)") (class "Default")
      (node (ref "U8") (pin "R13") (pinfunction "NC_R13") (pintype "passive+no_connect"))
    )
    (net (code "55") (name "unconnected-(U8H-NC-PadR15)") (class "Default")
      (node (ref "U8") (pin "R15") (pinfunction "NC_R15") (pintype "passive+no_connect"))
    )
    (net (code "56") (name "unconnected-(U8H-NC-PadR16)") (class "Default")
      (node (ref "U8") (pin "R16") (pinfunction "NC_R16") (pintype "passive+no_connect"))
    )
    (net (code "57") (name "unconnected-(U8H-NC-PadT7)") (class "Default")
      (node (ref "U8") (pin "T7") (pinfunction "NC_T7") (pintype "passive+no_connect"))
    )
    (net (code "58") (name "unconnected-(U8H-NC-PadT8)") (class "Default")
      (node (ref "U8") (pin "T8") (pinfunction "NC_T8") (pintype "passive+no_connect"))
    )
    (net (code "59") (name "unconnected-(U8H-NC-PadT10)") (class "Default")
      (node (ref "U8") (pin "T10") (pinfunction "NC_T10") (pintype "passive+no_connect"))
    )
    (net (code "60") (name "unconnected-(U8H-NC-PadT11)") (class "Default")
      (node (ref "U8") (pin "T11") (pinfunction "NC_T11") (pintype "passive+no_connect"))
    )
    (net (code "61") (name "unconnected-(U8H-NC-PadT12)") (class "Default")
      (node (ref "U8") (pin "T12") (pinfunction "NC_T12") (pintype "passive+no_connect"))
    )
    (net (code "62") (name "unconnected-(U8H-NC-PadT14)") (class "Default")
      (node (ref "U8") (pin "T14") (pinfunction "NC_T14") (pintype "passive+no_connect"))
    )
    (net (code "63") (name "unconnected-(U8H-NC-PadT15)") (class "Default")
      (node (ref "U8") (pin "T15") (pinfunction "NC_T15") (pintype "passive+no_connect"))
    )
    (net (code "64") (name "unconnected-(U8H-NC-PadT16)") (class "Default")
      (node (ref "U8") (pin "T16") (pinfunction "NC_T16") (pintype "passive+no_connect"))
    )
    (net (code "65") (name "unconnected-(U8H-NC-PadU6)") (class "Default")
      (node (ref "U8") (pin "U6") (pinfunction "NC_U6") (pintype "passive+no_connect"))
    )
    (net (code "66") (name "unconnected-(U8H-NC-PadU8)") (class "Default")
      (node (ref "U8") (pin "U8") (pinfunction "NC_U8") (pintype "passive+no_connect"))
    )
    (net (code "67") (name "unconnected-(U8H-NC-PadU9)") (class "Default")
      (node (ref "U8") (pin "U9") (pinfunction "NC_U9") (pintype "passive+no_connect"))
    )
    (net (code "68") (name "unconnected-(U8H-NC-PadU10)") (class "Default")
      (node (ref "U8") (pin "U10") (pinfunction "NC_U10") (pintype "passive+no_connect"))
    )
    (net (code "69") (name "unconnected-(U8H-NC-PadU12)") (class "Default")
      (node (ref "U8") (pin "U12") (pinfunction "NC_U12") (pintype "passive+no_connect"))
    )
    (net (code "70") (name "unconnected-(U8H-NC-PadU16)") (class "Default")
      (node (ref "U8") (pin "U16") (pinfunction "NC_U16") (pintype "passive+no_connect"))
    )
    (net (code "71") (name "unconnected-(U8H-NC-PadU17)") (class "Default")
      (node (ref "U8") (pin "U17") (pinfunction "NC_U17") (pintype "passive+no_connect"))
    )
    (net (code "72") (name "unconnected-(U8H-NC-PadV5)") (class "Default")
      (node (ref "U8") (pin "V5") (pinfunction "NC_V5") (pintype "passive+no_connect"))
    )
    (net (code "73") (name "unconnected-(U8H-NC-PadV7)") (class "Default")
      (node (ref "U8") (pin "V7") (pinfunction "NC_V7") (pintype "passive+no_connect"))
    )
    (net (code "74") (name "unconnected-(U8H-NC-PadV9)") (class "Default")
      (node (ref "U8") (pin "V9") (pinfunction "NC_V9") (pintype "passive+no_connect"))
    )
    (net (code "75") (name "unconnected-(U8H-NC-PadV13)") (class "Default")
      (node (ref "U8") (pin "V13") (pinfunction "NC_V13") (pintype "passive+no_connect"))
    )
    (net (code "76") (name "unconnected-(U8H-NC-PadV17)") (class "Default")
      (node (ref "U8") (pin "V17") (pinfunction "NC_V17") (pintype "passive+no_connect"))
    )
    (net (code "77") (name "unconnected-(U8H-NC-PadV18)") (class "Default")
      (node (ref "U8") (pin "V18") (pinfunction "NC_V18") (pintype "passive+no_connect"))
    )
    (net (code "78") (name "unconnected-(U8H-NC-PadV19)") (class "Default")
      (node (ref "U8") (pin "V19") (pinfunction "NC_V19") (pintype "passive+no_connect"))
    )
    (net (code "79") (name "unconnected-(U8H-NC-PadW6)") (class "Default")
      (node (ref "U8") (pin "W6") (pinfunction "NC_W6") (pintype "passive+no_connect"))
    )
    (net (code "80") (name "unconnected-(U8H-NC-PadW8)") (class "Default")
      (node (ref "U8") (pin "W8") (pinfunction "NC_W8") (pintype "passive+no_connect"))
    )
    (net (code "81") (name "unconnected-(U8H-NC-PadW9)") (class "Default")
      (node (ref "U8") (pin "W9") (pinfunction "NC_W9") (pintype "passive+no_connect"))
    )
    (net (code "82") (name "unconnected-(U8H-NC-PadW10)") (class "Default")
      (node (ref "U8") (pin "W10") (pinfunction "NC_W10") (pintype "passive+no_connect"))
    )
    (net (code "83") (name "unconnected-(U8H-NC-PadW13)") (class "Default")
      (node (ref "U8") (pin "W13") (pinfunction "NC_W13") (pintype "passive+no_connect"))
    )
    (net (code "84") (name "unconnected-(U8H-NC-PadW14)") (class "Default")
      (node (ref "U8") (pin "W14") (pinfunction "NC_W14") (pintype "passive+no_connect"))
    )
    (net (code "85") (name "unconnected-(U8H-NC-PadW15)") (class "Default")
      (node (ref "U8") (pin "W15") (pinfunction "NC_W15") (pintype "passive+no_connect"))
    )
    (net (code "86") (name "unconnected-(U8H-NC-PadW17)") (class "Default")
      (node (ref "U8") (pin "W17") (pinfunction "NC_W17") (pintype "passive+no_connect"))
    )
    (net (code "87") (name "unconnected-(U8H-NC-PadW18)") (class "Default")
      (node (ref "U8") (pin "W18") (pinfunction "NC_W18") (pintype "passive+no_connect"))
    )
    (net (code "88") (name "unconnected-(U8H-NC-PadY5)") (class "Default")
      (node (ref "U8") (pin "Y5") (pinfunction "NC_Y5") (pintype "passive+no_connect"))
    )
    (net (code "89") (name "unconnected-(U8H-NC-PadY6)") (class "Default")
      (node (ref "U8") (pin "Y6") (pinfunction "NC_Y6") (pintype "passive+no_connect"))
    )
    (net (code "90") (name "unconnected-(U8H-NC-PadY8)") (class "Default")
      (node (ref "U8") (pin "Y8") (pinfunction "NC_Y8") (pintype "passive+no_connect"))
    )
    (net (code "91") (name "unconnected-(U8H-NC-PadY10)") (class "Default")
      (node (ref "U8") (pin "Y10") (pinfunction "NC_Y10") (pintype "passive+no_connect"))
    )
    (net (code "92") (name "unconnected-(U8H-NC-PadY14)") (class "Default")
      (node (ref "U8") (pin "Y14") (pinfunction "NC_Y14") (pintype "passive+no_connect"))
    )
    (net (code "93") (name "unconnected-(U8H-NC-PadY16)") (class "Default")
      (node (ref "U8") (pin "Y16") (pinfunction "NC_Y16") (pintype "passive+no_connect"))
    )
    (net (code "94") (name "unconnected-(U8H-NC-PadY18)") (class "Default")
      (node (ref "U8") (pin "Y18") (pinfunction "NC_Y18") (pintype "passive+no_connect"))
    )
    (net (code "95") (name "unconnected-(U9E-CTRL_2V5-Pad46)") (class "Default")
      (node (ref "U9") (pin "46") (pinfunction "CTRL_2V5_46") (pintype "passive+no_connect"))
    )
    (net (code "96") (name "unconnected-(U9E-NC-Pad7)") (class "Default")
      (node (ref "U9") (pin "7") (pinfunction "NC_7") (pintype "passive+no_connect"))
    )
    (net (code "97") (name "unconnected-(U9E-NC-Pad8)") (class "Default")
      (node (ref "U9") (pin "8") (pinfunction "NC_8") (pintype "passive+no_connect"))
    )
    (net (code "98") (name "unconnected-(U9E-NC-Pad9)") (class "Default")
      (node (ref "U9") (pin "9") (pinfunction "NC_9") (pintype "passive+no_connect"))
    )
    (net (code "99") (name "unconnected-(U9E-NC-Pad10)") (class "Default")
      (node (ref "U9") (pin "10") (pinfunction "NC_10") (pintype "passive+no_connect"))
    )
    (net (code "100") (name "unconnected-(U9E-NC-Pad11)") (class "Default")
      (node (ref "U9") (pin "11") (pinfunction "NC_11") (pintype "passive+no_connect"))
    )
    (net (code "101") (name "unconnected-(U11B-NC-Pad14)") (class "Default")
      (node (ref "U11") (pin "14") (pinfunction "NC_14") (pintype "passive+no_connect"))
    )
    (net (code "102") (name "unconnected-(U11B-NC-Pad16)") (class "Default")
      (node (ref "U11") (pin "16") (pinfunction "NC_16") (pintype "passive+no_connect"))
    )
    (net (code "103") (name "unconnected-(U11B-NC-Pad66)") (class "Default")
      (node (ref "U11") (pin "66") (pinfunction "NC_66") (pintype "passive+no_connect"))
    )
    (net (code "104") (name "unconnected-(U15-VREF-Pad6)") (class "Default")
      (node (ref "U15") (pin "6") (pinfunction "VREF_6") (pintype "power_in+no_connect"))
    )
    (net (code "105") (name "unconnected-(U16-VREF-Pad6)") (class "Default")
      (node (ref "U16") (pin "6") (pinfunction "VREF_6") (pintype "power_in+no_connect"))
    )
    (net (code "106") (name "unconnected-(U34-VREF-Pad6)") (class "Default")
      (node (ref "U34") (pin "6") (pinfunction "VREF_6") (pintype "power_in+no_connect"))
    )
    (net (code "107") (name "unconnected-(X5'-Pad3)") (class "Default")
      (node (ref "X5'") (pin "3") (pinfunction "3_3") (pintype "passive+no_connect"))
    )
  )
)
